# Schematic_2023-08-02.net
KiCad netlist of a schematic drawn in Altium Designer
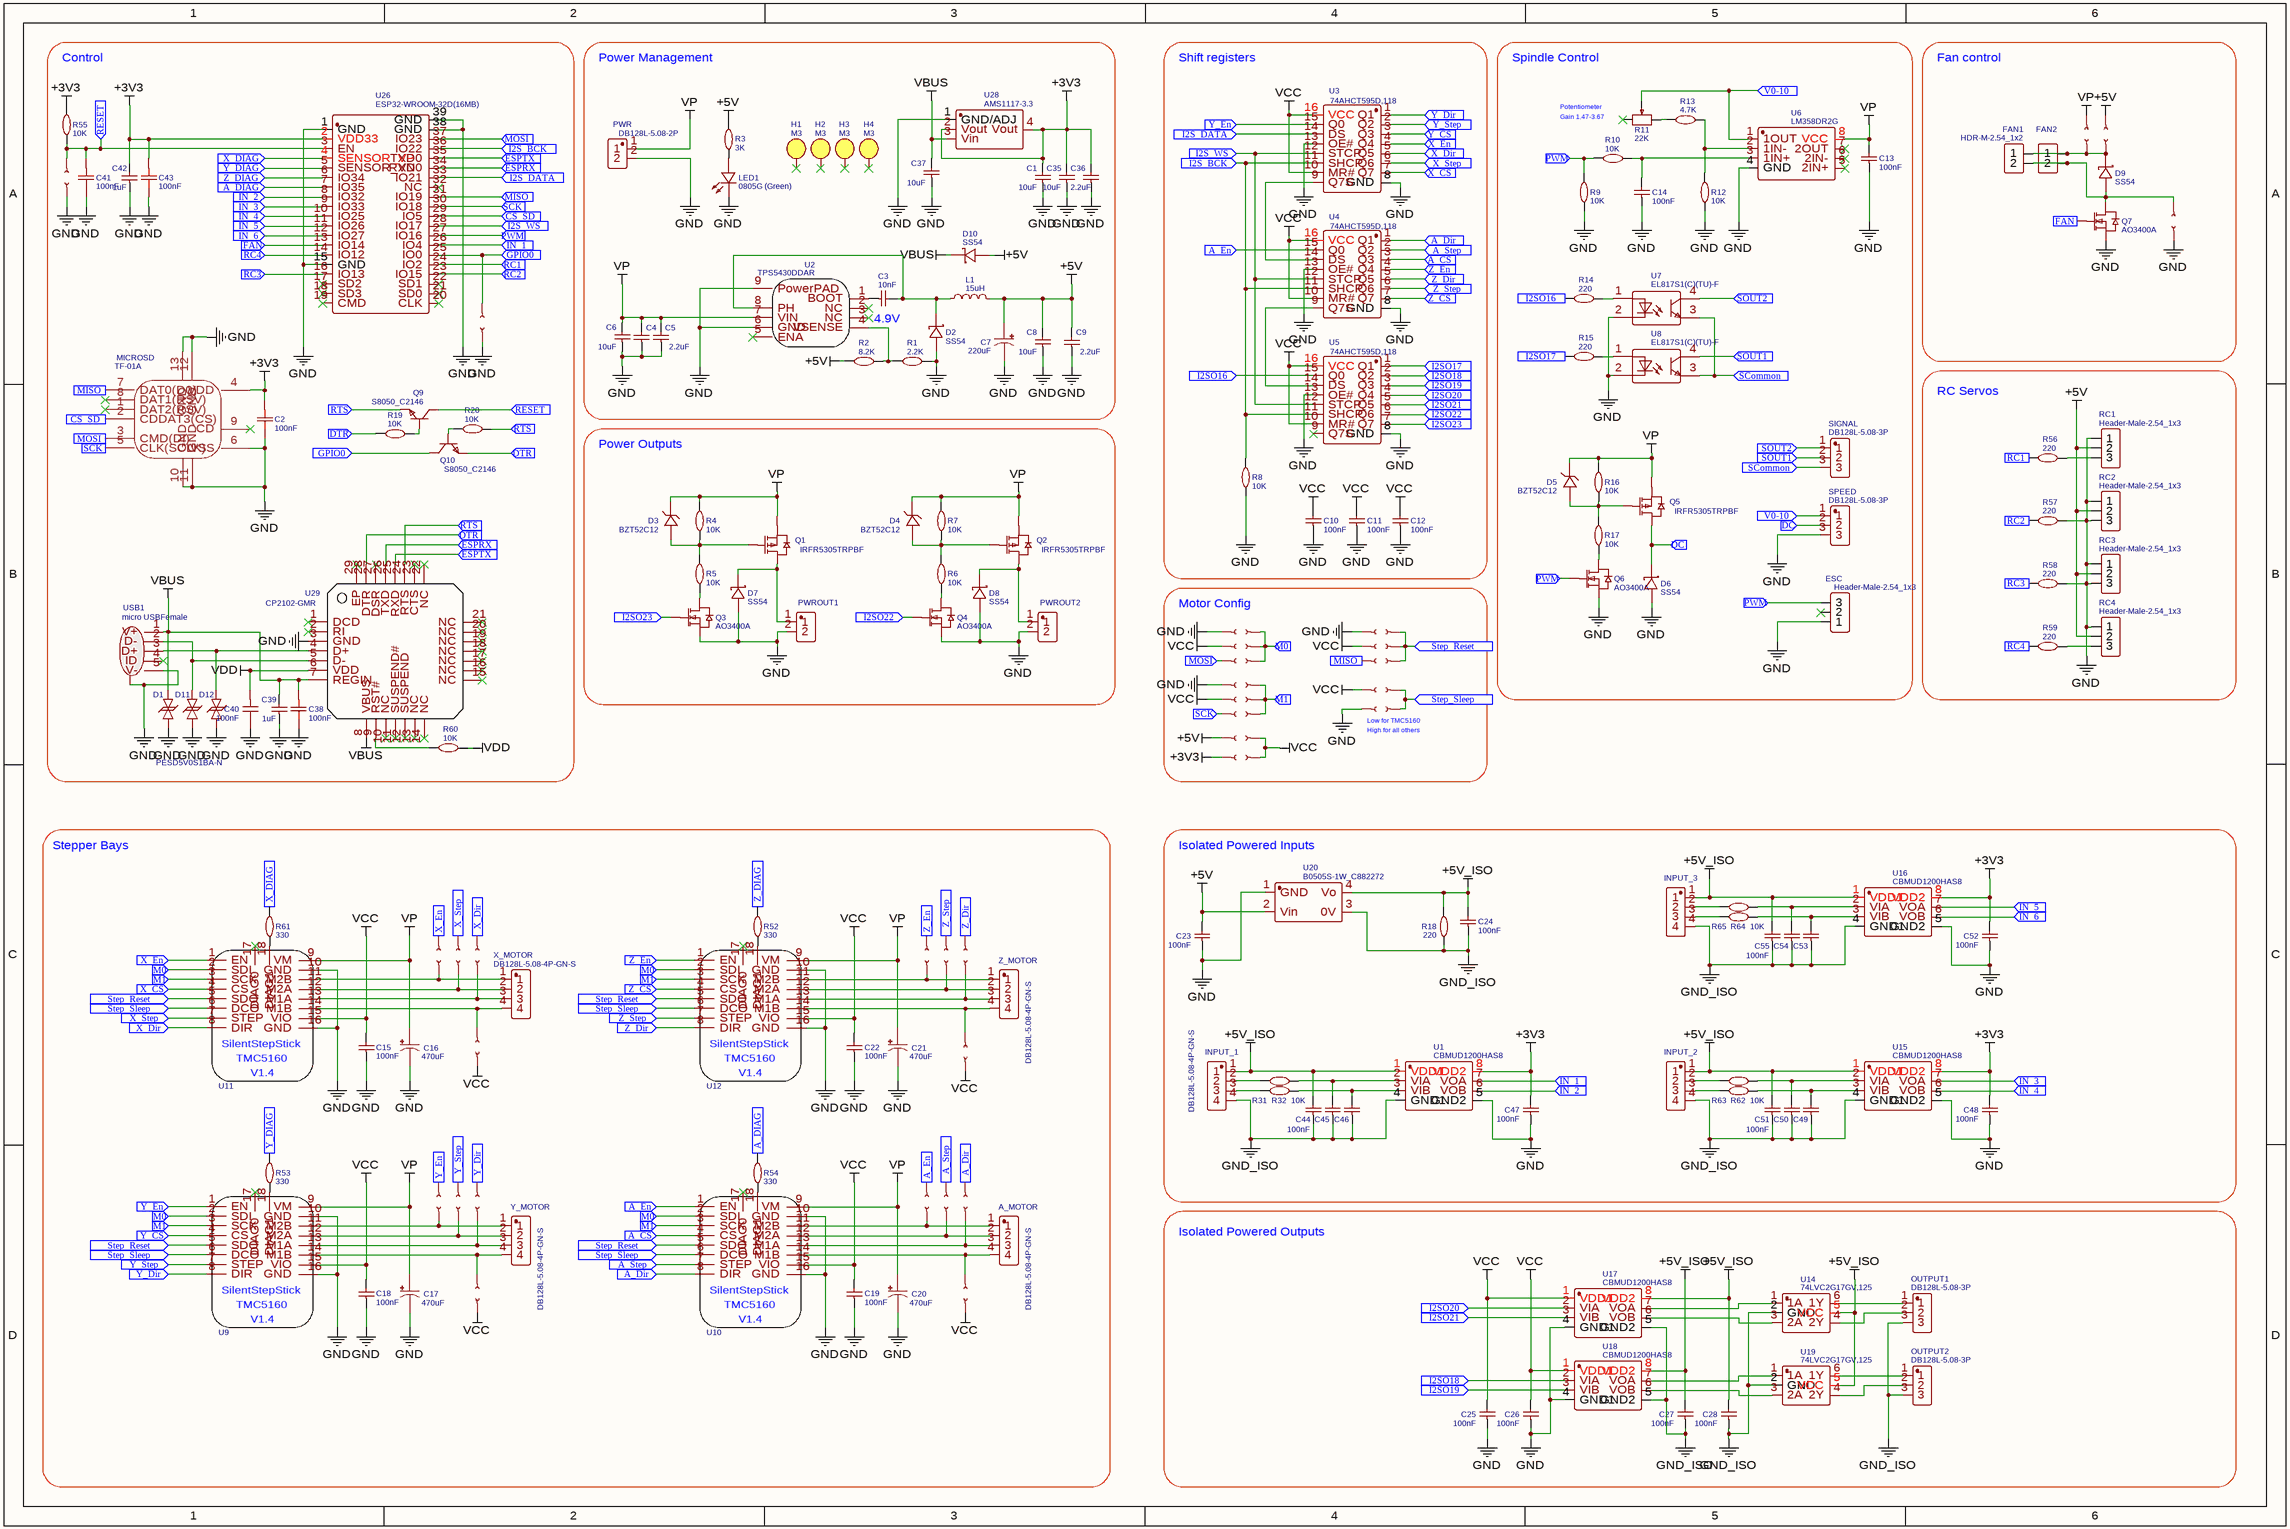
[diagram p0: Schematic_2023-08-02.schdoc]

(export (version "E")
  (design (tool "Eeschema 10.0.6"))
  (components
    (comp (ref "A_MOTOR")
      (value "DB128L-5.08-4P-GN-S")
      (footprint "CONN-TH_4P-5.00_DB128L-5.0-4P-BU-S")
      (fields (field (name "MANUFACTURER") "DIBO") (field (name "CONTRIBUTOR") "LCSC"))
      (libsource (lib "") (part "root_0_DB128L-5.08-4P-GN-S__1"))
    )
    (comp (ref "C1")
      (value "10uF")
      (footprint "C1206")
      (fields (field (name "MANUFACTURER PART") "CL31A106KBHNNNE") (field (name "MANUFACTURER") "SAMSUNG"))
      (libsource (lib "altium-import") (part "root_1_10uF_"))
    )
    (comp (ref "C2")
      (value "100nF")
      (footprint "C0603")
      (fields (field (name "MANUFACTURER") "YAGEO") (field (name "MANUFACTURER PART") "CC0603KRX7R9BB104"))
      (libsource (lib "altium-import") (part "root_1_100nF_"))
    )
    (comp (ref "C3")
      (value "10nF")
      (footprint "C0805")
      (fields (field (name "MANUFACTURER PART") "CL21B103KBANNNC") (field (name "MANUFACTURER") "SAMSUNG"))
      (libsource (lib "altium-import") (part "root_0_10nF_"))
    )
    (comp (ref "C4")
      (value "2.2uF")
      (footprint "C1206")
      (fields (field (name "MANUFACTURER PART") "CL31B225KBHNNNE") (field (name "MANUFACTURER") "SAMSUNG"))
      (libsource (lib "") (part "root_1_2.2uF__1"))
    )
    (comp (ref "C5")
      (value "2.2uF")
      (footprint "C1206")
      (fields (field (name "MANUFACTURER PART") "CL31B225KBHNNNE") (field (name "MANUFACTURER") "SAMSUNG"))
      (libsource (lib "") (part "root_1_2.2uF__1"))
    )
    (comp (ref "C6")
      (value "10uF")
      (footprint "C1206")
      (fields (field (name "MANUFACTURER PART") "CL31A106KBHNNNE") (field (name "MANUFACTURER") "SAMSUNG"))
      (libsource (lib "altium-import") (part "root_1_10uF_"))
    )
    (comp (ref "C7")
      (value "220uF")
      (footprint "CAP-SMD_L7.3-W4.3-R-RD")
      (fields
        (field (name "MANUFACTURER") "TORCH")
        (field (name "MANUFACTURER PART") "CA45-D-10V-220μF-K")
        (field (name "CONTRIBUTOR") "LCSC")
      )
      (libsource (lib "altium-import") (part "root_1_220uF_"))
    )
    (comp (ref "C8")
      (value "10uF")
      (footprint "C1206")
      (fields (field (name "MANUFACTURER PART") "CL31A106KBHNNNE") (field (name "MANUFACTURER") "SAMSUNG"))
      (libsource (lib "altium-import") (part "root_1_10uF_"))
    )
    (comp (ref "C9")
      (value "2.2uF")
      (footprint "C1206")
      (fields (field (name "MANUFACTURER PART") "CL31B225KBHNNNE") (field (name "MANUFACTURER") "SAMSUNG"))
      (libsource (lib "") (part "root_1_2.2uF__1"))
    )
    (comp (ref "C10")
      (value "100nF")
      (footprint "C0805")
      (fields (field (name "MANUFACTURER PART") "CC0805KRX7R9BB104") (field (name "MANUFACTURER") "YAGEO"))
      (libsource (lib "") (part "root_1_100nF__1"))
    )
    (comp (ref "C11")
      (value "100nF")
      (footprint "C0805")
      (fields (field (name "MANUFACTURER PART") "CC0805KRX7R9BB104") (field (name "MANUFACTURER") "YAGEO"))
      (libsource (lib "") (part "root_1_100nF__1"))
    )
    (comp (ref "C12")
      (value "100nF")
      (footprint "C0805")
      (fields (field (name "MANUFACTURER PART") "CC0805KRX7R9BB104") (field (name "MANUFACTURER") "YAGEO"))
      (libsource (lib "") (part "root_1_100nF__1"))
    )
    (comp (ref "C13")
      (value "100nF")
      (footprint "C0805")
      (fields (field (name "MANUFACTURER PART") "CC0805KRX7R9BB104") (field (name "MANUFACTURER") "YAGEO"))
      (libsource (lib "") (part "root_1_100nF__1"))
    )
    (comp (ref "C14")
      (value "100nF")
      (footprint "C0805")
      (fields (field (name "MANUFACTURER PART") "CC0805KRX7R9BB104") (field (name "MANUFACTURER") "YAGEO"))
      (libsource (lib "") (part "root_1_100nF__1"))
    )
    (comp (ref "C15")
      (value "100nF")
      (footprint "C0805")
      (fields (field (name "MANUFACTURER PART") "CC0805KRX7R9BB104") (field (name "MANUFACTURER") "YAGEO"))
      (libsource (lib "") (part "root_1_100nF__1"))
    )
    (comp (ref "C16")
      (value "470uF")
      (footprint "CAP-SMD_BD12.5-L13.0-W13.0-FD")
      (fields
        (field (name "MANUFACTURER") "Changzhou Huawei Elec")
        (field (name "MANUFACTURER PART") "VT1H471MI135000CE0")
        (field (name "CONTRIBUTOR") "LCSC")
      )
      (libsource (lib "altium-import") (part "root_0_470uF_"))
    )
    (comp (ref "C17")
      (value "470uF")
      (footprint "CAP-SMD_BD12.5-L13.0-W13.0-FD")
      (fields
        (field (name "MANUFACTURER") "Changzhou Huawei Elec")
        (field (name "MANUFACTURER PART") "VT1H471MI135000CE0")
        (field (name "CONTRIBUTOR") "LCSC")
      )
      (libsource (lib "altium-import") (part "root_0_470uF_"))
    )
    (comp (ref "C18")
      (value "100nF")
      (footprint "C0805")
      (fields (field (name "MANUFACTURER PART") "CC0805KRX7R9BB104") (field (name "MANUFACTURER") "YAGEO"))
      (libsource (lib "") (part "root_1_100nF__1"))
    )
    (comp (ref "C19")
      (value "100nF")
      (footprint "C0805")
      (fields (field (name "MANUFACTURER PART") "CC0805KRX7R9BB104") (field (name "MANUFACTURER") "YAGEO"))
      (libsource (lib "") (part "root_1_100nF__1"))
    )
    (comp (ref "C20")
      (value "470uF")
      (footprint "CAP-SMD_BD12.5-L13.0-W13.0-FD")
      (fields
        (field (name "MANUFACTURER") "Changzhou Huawei Elec")
        (field (name "MANUFACTURER PART") "VT1H471MI135000CE0")
        (field (name "CONTRIBUTOR") "LCSC")
      )
      (libsource (lib "altium-import") (part "root_0_470uF_"))
    )
    (comp (ref "C21")
      (value "470uF")
      (footprint "CAP-SMD_BD12.5-L13.0-W13.0-FD")
      (fields
        (field (name "MANUFACTURER") "Changzhou Huawei Elec")
        (field (name "MANUFACTURER PART") "VT1H471MI135000CE0")
        (field (name "CONTRIBUTOR") "LCSC")
      )
      (libsource (lib "altium-import") (part "root_0_470uF_"))
    )
    (comp (ref "C22")
      (value "100nF")
      (footprint "C0805")
      (fields (field (name "MANUFACTURER PART") "CC0805KRX7R9BB104") (field (name "MANUFACTURER") "YAGEO"))
      (libsource (lib "") (part "root_1_100nF__1"))
    )
    (comp (ref "C23")
      (value "100nF")
      (footprint "C0805")
      (fields (field (name "MANUFACTURER PART") "CC0805KRX7R9BB104") (field (name "MANUFACTURER") "YAGEO"))
      (libsource (lib "") (part "root_1_100nF__2"))
    )
    (comp (ref "C24")
      (value "100nF")
      (footprint "C0805")
      (fields (field (name "MANUFACTURER PART") "CC0805KRX7R9BB104") (field (name "MANUFACTURER") "YAGEO"))
      (libsource (lib "") (part "root_1_100nF__1"))
    )
    (comp (ref "C25")
      (value "100nF")
      (footprint "C0805")
      (fields (field (name "MANUFACTURER PART") "CC0805KRX7R9BB104") (field (name "MANUFACTURER") "YAGEO"))
      (libsource (lib "") (part "root_1_100nF__2"))
    )
    (comp (ref "C26")
      (value "100nF")
      (footprint "C0805")
      (fields (field (name "MANUFACTURER PART") "CC0805KRX7R9BB104") (field (name "MANUFACTURER") "YAGEO"))
      (libsource (lib "") (part "root_1_100nF__2"))
    )
    (comp (ref "C27")
      (value "100nF")
      (footprint "C0805")
      (fields (field (name "MANUFACTURER PART") "CC0805KRX7R9BB104") (field (name "MANUFACTURER") "YAGEO"))
      (libsource (lib "") (part "root_1_100nF__2"))
    )
    (comp (ref "C28")
      (value "100nF")
      (footprint "C0805")
      (fields (field (name "MANUFACTURER PART") "CC0805KRX7R9BB104") (field (name "MANUFACTURER") "YAGEO"))
      (libsource (lib "") (part "root_1_100nF__2"))
    )
    (comp (ref "C35")
      (value "10uF")
      (footprint "C1206")
      (fields (field (name "MANUFACTURER PART") "CL31A106KBHNNNE") (field (name "MANUFACTURER") "SAMSUNG"))
      (libsource (lib "altium-import") (part "root_1_10uF_"))
    )
    (comp (ref "C36")
      (value "2.2uF")
      (footprint "C1206")
      (fields (field (name "MANUFACTURER PART") "CL31B225KBHNNNE") (field (name "MANUFACTURER") "SAMSUNG"))
      (libsource (lib "altium-import") (part "root_1_2.2uF_"))
    )
    (comp (ref "C37")
      (value "10uF")
      (footprint "C1206")
      (fields (field (name "MANUFACTURER PART") "CL31A106KBHNNNE") (field (name "MANUFACTURER") "SAMSUNG"))
      (libsource (lib "altium-import") (part "root_1_10uF_"))
    )
    (comp (ref "C38")
      (value "100nF")
      (footprint "C0603")
      (fields (field (name "MANUFACTURER") "YAGEO") (field (name "MANUFACTURER PART") "CC0603KRX7R9BB104"))
      (libsource (lib "altium-import") (part "root_1_100nF_"))
    )
    (comp (ref "C39")
      (value "1uF")
      (footprint "C0603")
      (fields (field (name "MANUFACTURER PART") "CL10A105KB8NNNC") (field (name "MANUFACTURER") "SAMSUNG"))
      (libsource (lib "altium-import") (part "root_1_1uF_"))
    )
    (comp (ref "C40")
      (value "100nF")
      (footprint "C0603")
      (fields (field (name "MANUFACTURER") "YAGEO") (field (name "MANUFACTURER PART") "CC0603KRX7R9BB104"))
      (libsource (lib "") (part "root_1_100nF__3"))
    )
    (comp (ref "C41")
      (value "100nF")
      (footprint "C0603")
      (fields (field (name "MANUFACTURER") "YAGEO") (field (name "MANUFACTURER PART") "CC0603KRX7R9BB104"))
      (libsource (lib "altium-import") (part "root_1_100nF_"))
    )
    (comp (ref "C42")
      (value "1uF")
      (footprint "C0603")
      (fields (field (name "MANUFACTURER PART") "CL10A105KB8NNNC") (field (name "MANUFACTURER") "SAMSUNG"))
      (libsource (lib "altium-import") (part "root_1_1uF_"))
    )
    (comp (ref "C43")
      (value "100nF")
      (footprint "C0603")
      (fields (field (name "MANUFACTURER") "YAGEO") (field (name "MANUFACTURER PART") "CC0603KRX7R9BB104"))
      (libsource (lib "altium-import") (part "root_1_100nF_"))
    )
    (comp (ref "C44")
      (value "100nF")
      (footprint "C0805")
      (fields (field (name "MANUFACTURER PART") "CC0805KRX7R9BB104") (field (name "MANUFACTURER") "YAGEO"))
      (libsource (lib "") (part "root_1_100nF__2"))
    )
    (comp (ref "C45")
      (value "100nF")
      (footprint "C0805")
      (fields (field (name "MANUFACTURER PART") "CC0805KRX7R9BB104") (field (name "MANUFACTURER") "YAGEO"))
      (libsource (lib "") (part "root_1_100nF__2"))
    )
    (comp (ref "C46")
      (value "100nF")
      (footprint "C0805")
      (fields (field (name "MANUFACTURER PART") "CC0805KRX7R9BB104") (field (name "MANUFACTURER") "YAGEO"))
      (libsource (lib "") (part "root_1_100nF__2"))
    )
    (comp (ref "C47")
      (value "100nF")
      (footprint "C0805")
      (fields (field (name "MANUFACTURER PART") "CC0805KRX7R9BB104") (field (name "MANUFACTURER") "YAGEO"))
      (libsource (lib "") (part "root_1_100nF__2"))
    )
    (comp (ref "C48")
      (value "100nF")
      (footprint "C0805")
      (fields (field (name "MANUFACTURER PART") "CC0805KRX7R9BB104") (field (name "MANUFACTURER") "YAGEO"))
      (libsource (lib "") (part "root_1_100nF__2"))
    )
    (comp (ref "C49")
      (value "100nF")
      (footprint "C0805")
      (fields (field (name "MANUFACTURER PART") "CC0805KRX7R9BB104") (field (name "MANUFACTURER") "YAGEO"))
      (libsource (lib "") (part "root_1_100nF__2"))
    )
    (comp (ref "C50")
      (value "100nF")
      (footprint "C0805")
      (fields (field (name "MANUFACTURER PART") "CC0805KRX7R9BB104") (field (name "MANUFACTURER") "YAGEO"))
      (libsource (lib "") (part "root_1_100nF__2"))
    )
    (comp (ref "C51")
      (value "100nF")
      (footprint "C0805")
      (fields (field (name "MANUFACTURER PART") "CC0805KRX7R9BB104") (field (name "MANUFACTURER") "YAGEO"))
      (libsource (lib "") (part "root_1_100nF__2"))
    )
    (comp (ref "C52")
      (value "100nF")
      (footprint "C0805")
      (fields (field (name "MANUFACTURER PART") "CC0805KRX7R9BB104") (field (name "MANUFACTURER") "YAGEO"))
      (libsource (lib "") (part "root_1_100nF__2"))
    )
    (comp (ref "C53")
      (value "100nF")
      (footprint "C0805")
      (fields (field (name "MANUFACTURER PART") "CC0805KRX7R9BB104") (field (name "MANUFACTURER") "YAGEO"))
      (libsource (lib "") (part "root_1_100nF__2"))
    )
    (comp (ref "C54")
      (value "100nF")
      (footprint "C0805")
      (fields (field (name "MANUFACTURER PART") "CC0805KRX7R9BB104") (field (name "MANUFACTURER") "YAGEO"))
      (libsource (lib "") (part "root_1_100nF__2"))
    )
    (comp (ref "C55")
      (value "100nF")
      (footprint "C0805")
      (fields (field (name "MANUFACTURER PART") "CC0805KRX7R9BB104") (field (name "MANUFACTURER") "YAGEO"))
      (libsource (lib "") (part "root_1_100nF__2"))
    )
    (comp (ref "D1")
      (value "PESD5V0S1BA-N")
      (footprint "SOD-323_L1.8-W1.3-LS2.5-BI")
      (fields (field (name "MANUFACTURER") "Bourne Semicon (Shenzhen)") (field (name "CONTRIBUTOR") "LCSC"))
      (libsource (lib "altium-import") (part "root_1_PESD5V0S1BA-N_"))
    )
    (comp (ref "D2")
      (value "SS54")
      (footprint "SMA_L4.4-W2.8-LS5.4-R-RD")
      (fields (field (name "MANUFACTURER") "MDD"))
      (libsource (lib "altium-import") (part "root_3_SS54_"))
    )
    (comp (ref "D3")
      (value "BZT52C12")
      (footprint "SOD-123_L2.7-W1.6-LS3.7-RD")
      (fields (field (name "MANUFACTURER") "MDD") (field (name "CONTRIBUTOR") "LCSC"))
      (libsource (lib "altium-import") (part "root_3_BZT52C12_"))
    )
    (comp (ref "D4")
      (value "BZT52C12")
      (footprint "SOD-123_L2.7-W1.6-LS3.7-RD")
      (fields (field (name "MANUFACTURER") "MDD") (field (name "CONTRIBUTOR") "LCSC"))
      (libsource (lib "altium-import") (part "root_3_BZT52C12_"))
    )
    (comp (ref "D5")
      (value "BZT52C12")
      (footprint "SOD-123_L2.7-W1.6-LS3.7-RD")
      (fields (field (name "MANUFACTURER") "MDD") (field (name "CONTRIBUTOR") "LCSC"))
      (libsource (lib "altium-import") (part "root_3_BZT52C12_"))
    )
    (comp (ref "D6")
      (value "SS54")
      (footprint "SMA_L4.4-W2.8-LS5.4-R-RD")
      (fields (field (name "MANUFACTURER") "MDD"))
      (libsource (lib "altium-import") (part "root_3_SS54_"))
    )
    (comp (ref "D7")
      (value "SS54")
      (footprint "SMA_L4.4-W2.8-LS5.4-R-RD")
      (fields (field (name "MANUFACTURER") "MDD"))
      (libsource (lib "altium-import") (part "root_3_SS54_"))
    )
    (comp (ref "D8")
      (value "SS54")
      (footprint "SMA_L4.4-W2.8-LS5.4-R-RD")
      (fields (field (name "MANUFACTURER") "MDD"))
      (libsource (lib "altium-import") (part "root_3_SS54_"))
    )
    (comp (ref "D9")
      (value "SS54")
      (footprint "SMA_L4.4-W2.8-LS5.4-R-RD")
      (fields (field (name "MANUFACTURER") "MDD"))
      (libsource (lib "altium-import") (part "root_3_SS54_"))
    )
    (comp (ref "D10")
      (value "SS54")
      (footprint "SMA_L4.4-W2.8-LS5.4-R-RD")
      (fields (field (name "MANUFACTURER") "MDD"))
      (libsource (lib "altium-import") (part "root_0_SS54_"))
    )
    (comp (ref "D11")
      (value "PESD5V0S1BA-N")
      (footprint "SOD-323_L1.8-W1.3-LS2.5-BI")
      (fields (field (name "MANUFACTURER") "Bourne Semicon (Shenzhen)") (field (name "CONTRIBUTOR") "LCSC"))
      (libsource (lib "altium-import") (part "root_1_PESD5V0S1BA-N_"))
    )
    (comp (ref "D12")
      (value "PESD5V0S1BA-N")
      (footprint "SOD-323_L1.8-W1.3-LS2.5-BI")
      (fields (field (name "MANUFACTURER") "Bourne Semicon (Shenzhen)") (field (name "CONTRIBUTOR") "LCSC"))
      (libsource (lib "altium-import") (part "root_1_PESD5V0S1BA-N_"))
    )
    (comp (ref "ESC")
      (value "Header-Male-2.54_1x3")
      (footprint "HDR-TH_3P-P2.54-V-M-1")
      (fields (field (name "MANUFACTURER") "BOOMELE") (field (name "MANUFACTURER PART") "Header2.54mm 1*3P"))
      (libsource (lib "altium-import") (part "root_2_Header-Male-2.54_1x3_"))
    )
    (comp (ref "FAN1")
      (value "HDR-M-2.54_1x2")
      (footprint "HDR-M-2.54_1X2")
      (fields (field (name "CONTRIBUTOR") "LCEDA_Lib"))
      (libsource (lib "altium-import") (part "root_0_HDR-M-2.54_1x2_"))
    )
    (comp (ref "FAN2")
      (value "HDR-M-2.54_1x2")
      (footprint "HDR-M-2.54_1X2")
      (fields (field (name "CONTRIBUTOR") "LCEDA_Lib"))
      (libsource (lib "altium-import") (part "root_0_HDR-M-2.54_1x2_"))
    )
    (comp (ref "H1")
      (value "M3")
      (footprint "M3 CHASSIS")
      (fields (field (name "CONTRIBUTOR") "maitrai"))
      (libsource (lib "altium-import") (part "root_0_M3_"))
    )
    (comp (ref "H2")
      (value "M3")
      (footprint "M3 CHASSIS")
      (fields (field (name "CONTRIBUTOR") "maitrai"))
      (libsource (lib "altium-import") (part "root_0_M3_"))
    )
    (comp (ref "H3")
      (value "M3")
      (footprint "M3 CHASSIS")
      (fields (field (name "CONTRIBUTOR") "maitrai"))
      (libsource (lib "altium-import") (part "root_0_M3_"))
    )
    (comp (ref "H4")
      (value "M3")
      (footprint "M3 CHASSIS")
      (fields (field (name "CONTRIBUTOR") "maitrai"))
      (libsource (lib "altium-import") (part "root_0_M3_"))
    )
    (comp (ref "INPUT_1")
      (value "DB128L-5.08-4P-GN-S")
      (footprint "CONN-TH_4P-5.00_DB128L-5.0-4P-BU-S")
      (fields (field (name "MANUFACTURER") "DIBO") (field (name "CONTRIBUTOR") "LCSC"))
      (libsource (lib "altium-import") (part "root_0_DB128L-5.08-4P-GN-S_"))
    )
    (comp (ref "INPUT_2")
      (value "DB128L-5.08-4P-GN-S")
      (footprint "CONN-TH_4P-5.00_DB128L-5.0-4P-BU-S")
      (fields (field (name "MANUFACTURER") "DIBO") (field (name "CONTRIBUTOR") "LCSC"))
      (libsource (lib "altium-import") (part "root_0_DB128L-5.08-4P-GN-S_"))
    )
    (comp (ref "INPUT_3")
      (value "DB128L-5.08-4P-GN-S")
      (footprint "CONN-TH_4P-5.00_DB128L-5.0-4P-BU-S")
      (fields (field (name "MANUFACTURER") "DIBO") (field (name "CONTRIBUTOR") "LCSC"))
      (libsource (lib "altium-import") (part "root_0_DB128L-5.08-4P-GN-S_"))
    )
    (comp (ref "JP1")
      (value "JUMPER-PAD-2")
      (footprint "JUMPER_SOLDER_2")
      (fields (field (name "CONTRIBUTOR") "IPR SYSTEMS EDA"))
      (libsource (lib "altium-import") (part "root_1_JUMPER-PAD-2_"))
    )
    (comp (ref "JP2")
      (value "JUMPER-PAD-2")
      (footprint "JUMPER_SOLDER_2")
      (fields (field (name "CONTRIBUTOR") "IPR SYSTEMS EDA"))
      (libsource (lib "altium-import") (part "root_1_JUMPER-PAD-2_"))
    )
    (comp (ref "JP3")
      (value "JUMPER-PAD-2")
      (footprint "JUMPER_SOLDER_2")
      (fields (field (name "CONTRIBUTOR") "IPR SYSTEMS EDA"))
      (libsource (lib "altium-import") (part "root_1_JUMPER-PAD-2_"))
    )
    (comp (ref "JP4")
      (value "JUMPER-PAD-2")
      (footprint "JUMPER_SOLDER_2")
      (fields (field (name "CONTRIBUTOR") "IPR SYSTEMS EDA"))
      (libsource (lib "altium-import") (part "root_1_JUMPER-PAD-2_"))
    )
    (comp (ref "JP5")
      (value "JUMPER-PAD-2")
      (footprint "JUMPER_SOLDER_2")
      (fields (field (name "CONTRIBUTOR") "IPR SYSTEMS EDA"))
      (libsource (lib "altium-import") (part "root_0_JUMPER-PAD-2_"))
    )
    (comp (ref "JP6")
      (value "JUMPER-PAD-2")
      (footprint "JUMPER_SOLDER_2")
      (fields (field (name "CONTRIBUTOR") "IPR SYSTEMS EDA"))
      (libsource (lib "altium-import") (part "root_0_JUMPER-PAD-2_"))
    )
    (comp (ref "JP7")
      (value "JUMPER-PAD-2")
      (footprint "JUMPER_SOLDER_2")
      (fields (field (name "CONTRIBUTOR") "IPR SYSTEMS EDA"))
      (libsource (lib "altium-import") (part "root_0_JUMPER-PAD-2_"))
    )
    (comp (ref "JP8")
      (value "JUMPER-PAD-2")
      (footprint "JUMPER_SOLDER_2")
      (fields (field (name "CONTRIBUTOR") "IPR SYSTEMS EDA"))
      (libsource (lib "altium-import") (part "root_0_JUMPER-PAD-2_"))
    )
    (comp (ref "JP9")
      (value "JUMPER-PAD-2")
      (footprint "JUMPER_SOLDER_2")
      (fields (field (name "CONTRIBUTOR") "IPR SYSTEMS EDA"))
      (libsource (lib "altium-import") (part "root_0_JUMPER-PAD-2_"))
    )
    (comp (ref "JP10")
      (value "JUMPER-PAD-2")
      (footprint "JUMPER_SOLDER_2")
      (fields (field (name "CONTRIBUTOR") "IPR SYSTEMS EDA"))
      (libsource (lib "altium-import") (part "root_0_JUMPER-PAD-2_"))
    )
    (comp (ref "JP11")
      (value "JUMPER-PAD-2")
      (footprint "JUMPER_SOLDER_2")
      (fields (field (name "CONTRIBUTOR") "IPR SYSTEMS EDA"))
      (libsource (lib "altium-import") (part "root_0_JUMPER-PAD-2_"))
    )
    (comp (ref "JP12")
      (value "JUMPER-PAD-2")
      (footprint "JUMPER_SOLDER_2")
      (fields (field (name "CONTRIBUTOR") "IPR SYSTEMS EDA"))
      (libsource (lib "altium-import") (part "root_0_JUMPER-PAD-2_"))
    )
    (comp (ref "JP13")
      (value "JUMPER-PAD-2")
      (footprint "JUMPER_SOLDER_2")
      (fields (field (name "CONTRIBUTOR") "IPR SYSTEMS EDA"))
      (libsource (lib "altium-import") (part "root_0_JUMPER-PAD-2_"))
    )
    (comp (ref "JP14")
      (value "JUMPER-PAD-2")
      (footprint "JUMPER_SOLDER_2")
      (fields (field (name "CONTRIBUTOR") "IPR SYSTEMS EDA"))
      (libsource (lib "altium-import") (part "root_0_JUMPER-PAD-2_"))
    )
    (comp (ref "JP15")
      (value "JUMPER-PAD-2")
      (footprint "JUMPER_SOLDER_2")
      (fields (field (name "CONTRIBUTOR") "IPR SYSTEMS EDA"))
      (libsource (lib "altium-import") (part "root_1_JUMPER-PAD-2_"))
    )
    (comp (ref "JP16")
      (value "JUMPER-PAD-2")
      (footprint "JUMPER_SOLDER_2")
      (fields (field (name "CONTRIBUTOR") "IPR SYSTEMS EDA"))
      (libsource (lib "altium-import") (part "root_1_JUMPER-PAD-2_"))
    )
    (comp (ref "JP17")
      (value "JUMPER-PAD-2")
      (footprint "JUMPER_SOLDER_2")
      (fields (field (name "CONTRIBUTOR") "IPR SYSTEMS EDA"))
      (libsource (lib "altium-import") (part "root_1_JUMPER-PAD-2_"))
    )
    (comp (ref "JP18")
      (value "JUMPER-PAD-2")
      (footprint "JUMPER_SOLDER_2")
      (fields (field (name "CONTRIBUTOR") "IPR SYSTEMS EDA"))
      (libsource (lib "altium-import") (part "root_1_JUMPER-PAD-2_"))
    )
    (comp (ref "JP19")
      (value "JUMPER-PAD-2")
      (footprint "JUMPER_SOLDER_2")
      (fields (field (name "CONTRIBUTOR") "IPR SYSTEMS EDA"))
      (libsource (lib "altium-import") (part "root_1_JUMPER-PAD-2_"))
    )
    (comp (ref "JP20")
      (value "JUMPER-PAD-2")
      (footprint "JUMPER_SOLDER_2")
      (fields (field (name "CONTRIBUTOR") "IPR SYSTEMS EDA"))
      (libsource (lib "altium-import") (part "root_1_JUMPER-PAD-2_"))
    )
    (comp (ref "JP21")
      (value "JUMPER-PAD-2")
      (footprint "JUMPER_SOLDER_2")
      (fields (field (name "CONTRIBUTOR") "IPR SYSTEMS EDA"))
      (libsource (lib "altium-import") (part "root_1_JUMPER-PAD-2_"))
    )
    (comp (ref "JP22")
      (value "JUMPER-PAD-2")
      (footprint "JUMPER_SOLDER_2")
      (fields (field (name "CONTRIBUTOR") "IPR SYSTEMS EDA"))
      (libsource (lib "altium-import") (part "root_1_JUMPER-PAD-2_"))
    )
    (comp (ref "JP23")
      (value "JUMPER-PAD-2")
      (footprint "JUMPER_SOLDER_2")
      (fields (field (name "CONTRIBUTOR") "IPR SYSTEMS EDA"))
      (libsource (lib "altium-import") (part "root_1_JUMPER-PAD-2_"))
    )
    (comp (ref "JP24")
      (value "JUMPER-PAD-2")
      (footprint "JUMPER_SOLDER_2")
      (fields (field (name "CONTRIBUTOR") "IPR SYSTEMS EDA"))
      (libsource (lib "altium-import") (part "root_1_JUMPER-PAD-2_"))
    )
    (comp (ref "JP25")
      (value "JUMPER-PAD-2")
      (footprint "JUMPER_SOLDER_2")
      (fields (field (name "CONTRIBUTOR") "IPR SYSTEMS EDA"))
      (libsource (lib "altium-import") (part "root_1_JUMPER-PAD-2_"))
    )
    (comp (ref "JP26")
      (value "JUMPER-PAD-2")
      (footprint "JUMPER_SOLDER_2")
      (fields (field (name "CONTRIBUTOR") "IPR SYSTEMS EDA"))
      (libsource (lib "altium-import") (part "root_1_JUMPER-PAD-2_"))
    )
    (comp (ref "JP27")
      (value "JUMPER-PAD-2")
      (footprint "JUMPER_SOLDER_2")
      (fields (field (name "CONTRIBUTOR") "IPR SYSTEMS EDA"))
      (libsource (lib "altium-import") (part "root_1_JUMPER-PAD-2_"))
    )
    (comp (ref "JP28")
      (value "JUMPER-PAD-2")
      (footprint "JUMPER_SOLDER_2")
      (fields (field (name "CONTRIBUTOR") "IPR SYSTEMS EDA"))
      (libsource (lib "altium-import") (part "root_1_JUMPER-PAD-2_"))
    )
    (comp (ref "JP29")
      (value "JUMPER-PAD-2")
      (footprint "JUMPER_SOLDER_2")
      (fields (field (name "CONTRIBUTOR") "IPR SYSTEMS EDA"))
      (libsource (lib "altium-import") (part "root_1_JUMPER-PAD-2_"))
    )
    (comp (ref "JP30")
      (value "JUMPER-PAD-2")
      (footprint "JUMPER_SOLDER_2")
      (fields (field (name "CONTRIBUTOR") "IPR SYSTEMS EDA"))
      (libsource (lib "altium-import") (part "root_0_JUMPER-PAD-2_"))
    )
    (comp (ref "JP31")
      (value "JUMPER-PAD-2")
      (footprint "JUMPER_SOLDER_2")
      (fields (field (name "CONTRIBUTOR") "IPR SYSTEMS EDA"))
      (libsource (lib "altium-import") (part "root_0_JUMPER-PAD-2_"))
    )
    (comp (ref "JP32")
      (value "JUMPER-PAD-2")
      (footprint "JUMPER_SOLDER_2")
      (fields (field (name "CONTRIBUTOR") "IPR SYSTEMS EDA"))
      (libsource (lib "altium-import") (part "root_0_JUMPER-PAD-2_"))
    )
    (comp (ref "JP33")
      (value "JUMPER-PAD-2")
      (footprint "JUMPER_SOLDER_2")
      (fields (field (name "CONTRIBUTOR") "IPR SYSTEMS EDA"))
      (libsource (lib "altium-import") (part "root_1_JUMPER-PAD-2_"))
    )
    (comp (ref "JP34")
      (value "JUMPER-PAD-2")
      (footprint "JUMPER_SOLDER_2")
      (fields (field (name "CONTRIBUTOR") "IPR SYSTEMS EDA"))
      (libsource (lib "altium-import") (part "root_1_JUMPER-PAD-2_"))
    )
    (comp (ref "L1")
      (value "15uH")
      (footprint "IND-SMD_L7.3-W6.6")
      (fields (field (name "MANUFACTURER") "SXN") (field (name "MANUFACTURER PART") "SMMS0630-150M"))
      (libsource (lib "altium-import") (part "root_0_15uH_"))
    )
    (comp (ref "LED1")
      (value "0805G (Green)")
      (footprint "LED0805-RD_GREEN")
      (fields (field (name "MANUFACTURER") "KENTO"))
      (libsource (lib "altium-import") (part "root_1_0805G (Green)_"))
    )
    (comp (ref "MICROSD")
      (value "TF-01A")
      (footprint "TF-SMD_TF-01A")
      (fields (field (name "MANUFACTURER") "HRO"))
      (libsource (lib "altium-import") (part "root_0_TF-01A_"))
    )
    (comp (ref "OUTPUT1")
      (value "DB128L-5.08-3P")
      (footprint "CONN-TH_DB128L-5.08-3P")
      (fields (field (name "MANUFACTURER") "DIBO") (field (name "CONTRIBUTOR") "LCSC"))
      (libsource (lib "altium-import") (part "root_0_DB128L-5.08-3P_"))
    )
    (comp (ref "OUTPUT2")
      (value "DB128L-5.08-3P")
      (footprint "CONN-TH_DB128L-5.08-3P")
      (fields (field (name "MANUFACTURER") "DIBO") (field (name "CONTRIBUTOR") "LCSC"))
      (libsource (lib "altium-import") (part "root_0_DB128L-5.08-3P_"))
    )
    (comp (ref "PWR")
      (value "DB128L-5.08-2P")
      (footprint "CONN-TH_2P-P5.08_DB128L-5.08-2P")
      (fields (field (name "MANUFACTURER") "DIBO") (field (name "CONTRIBUTOR") "LCSC"))
      (libsource (lib "") (part "root_0_DB128L-5.08-2P__1"))
    )
    (comp (ref "PWROUT1")
      (value "DB128L-5.08-2P")
      (footprint "CONN-TH_2P-P5.08_DB128L-5.08-2P")
      (fields (field (name "MANUFACTURER") "DIBO") (field (name "CONTRIBUTOR") "LCSC"))
      (libsource (lib "altium-import") (part "root_0_DB128L-5.08-2P_"))
    )
    (comp (ref "PWROUT2")
      (value "DB128L-5.08-2P")
      (footprint "CONN-TH_2P-P5.08_DB128L-5.08-2P")
      (fields (field (name "MANUFACTURER") "DIBO") (field (name "CONTRIBUTOR") "LCSC"))
      (libsource (lib "altium-import") (part "root_0_DB128L-5.08-2P_"))
    )
    (comp (ref "Q1")
      (value "IRFR5305TRPBF")
      (footprint "TO-252-3_L6.5-W5.8-P4.58-TR")
      (fields (field (name "MANUFACTURER") "IR"))
      (libsource (lib "altium-import") (part "root_2_IRFR5305TRPBF_"))
    )
    (comp (ref "Q2")
      (value "IRFR5305TRPBF")
      (footprint "TO-252-3_L6.5-W5.8-P4.58-TR")
      (fields (field (name "MANUFACTURER") "IR"))
      (libsource (lib "altium-import") (part "root_2_IRFR5305TRPBF_"))
    )
    (comp (ref "Q3")
      (value "AO3400A")
      (footprint "SOT-23-3_L2.9-W1.6-P1.90-LS2.8-BR")
      (fields (field (name "MANUFACTURER") "AOS"))
      (libsource (lib "altium-import") (part "root_0_AO3400A_"))
    )
    (comp (ref "Q4")
      (value "AO3400A")
      (footprint "SOT-23-3_L2.9-W1.6-P1.90-LS2.8-BR")
      (fields (field (name "MANUFACTURER") "AOS"))
      (libsource (lib "altium-import") (part "root_0_AO3400A_"))
    )
    (comp (ref "Q5")
      (value "IRFR5305TRPBF")
      (footprint "TO-252-3_L6.5-W5.8-P4.58-TR")
      (fields (field (name "MANUFACTURER") "IR"))
      (libsource (lib "altium-import") (part "root_2_IRFR5305TRPBF_"))
    )
    (comp (ref "Q6")
      (value "AO3400A")
      (footprint "SOT-23-3_L2.9-W1.6-P1.90-LS2.8-BR")
      (fields (field (name "MANUFACTURER") "AOS"))
      (libsource (lib "altium-import") (part "root_0_AO3400A_"))
    )
    (comp (ref "Q7")
      (value "AO3400A")
      (footprint "SOT-23-3_L2.9-W1.6-P1.90-LS2.8-BR")
      (fields (field (name "MANUFACTURER") "AOS"))
      (libsource (lib "altium-import") (part "root_0_AO3400A_"))
    )
    (comp (ref "Q9")
      (value "S8050_C2146")
      (footprint "SOT-23-3_L3.0-W1.7-P0.95-LS2.9-BR")
      (fields (field (name "MANUFACTURER") "CJ") (field (name "MANUFACTURER PART") "S8050"))
      (libsource (lib "altium-import") (part "root_1_S8050_C2146_"))
    )
    (comp (ref "Q10")
      (value "S8050_C2146")
      (footprint "SOT-23-3_L3.0-W1.7-P0.95-LS2.9-BR")
      (fields (field (name "MANUFACTURER") "CJ") (field (name "MANUFACTURER PART") "S8050"))
      (libsource (lib "altium-import") (part "root_3_S8050_C2146_"))
    )
    (comp (ref "R1")
      (value "2.2K")
      (footprint "R0805")
      (fields (field (name "MANUFACTURER") "UniOhm") (field (name "MANUFACTURER PART") "0805W8F2201T5E"))
      (libsource (lib "altium-import") (part "root_0_2.2K_"))
    )
    (comp (ref "R2")
      (value "8.2K")
      (footprint "R0805")
      (fields (field (name "MANUFACTURER") "UniOhm") (field (name "MANUFACTURER PART") "0805W8F8201T5E"))
      (libsource (lib "altium-import") (part "root_0_8.2K_"))
    )
    (comp (ref "R3")
      (value "3K")
      (footprint "R0805")
      (fields (field (name "MANUFACTURER") "UniOhm") (field (name "MANUFACTURER PART") "0805W8F3001T5E"))
      (libsource (lib "altium-import") (part "root_1_3K_"))
    )
    (comp (ref "R4")
      (value "10K")
      (footprint "R0805")
      (fields (field (name "MANUFACTURER") "UniOhm") (field (name "MANUFACTURER PART") "0805W8F1002T5E"))
      (libsource (lib "altium-import") (part "root_3_10K_"))
    )
    (comp (ref "R5")
      (value "10K")
      (footprint "R0805")
      (fields (field (name "MANUFACTURER") "UniOhm") (field (name "MANUFACTURER PART") "0805W8F1002T5E"))
      (libsource (lib "altium-import") (part "root_3_10K_"))
    )
    (comp (ref "R6")
      (value "10K")
      (footprint "R0805")
      (fields (field (name "MANUFACTURER") "UniOhm") (field (name "MANUFACTURER PART") "0805W8F1002T5E"))
      (libsource (lib "altium-import") (part "root_3_10K_"))
    )
    (comp (ref "R7")
      (value "10K")
      (footprint "R0805")
      (fields (field (name "MANUFACTURER") "UniOhm") (field (name "MANUFACTURER PART") "0805W8F1002T5E"))
      (libsource (lib "altium-import") (part "root_3_10K_"))
    )
    (comp (ref "R8")
      (value "10K")
      (footprint "R0805")
      (fields (field (name "MANUFACTURER") "UniOhm") (field (name "MANUFACTURER PART") "0805W8F1002T5E"))
      (libsource (lib "altium-import") (part "root_3_10K_"))
    )
    (comp (ref "R9")
      (value "10K")
      (footprint "R0805")
      (fields (field (name "MANUFACTURER") "UniOhm") (field (name "MANUFACTURER PART") "0805W8F1002T5E"))
      (libsource (lib "altium-import") (part "root_3_10K_"))
    )
    (comp (ref "R10")
      (value "10K")
      (footprint "R0805")
      (fields (field (name "MANUFACTURER") "UniOhm") (field (name "MANUFACTURER PART") "0805W8F1002T5E"))
      (libsource (lib "altium-import") (part "root_0_10K_"))
    )
    (comp (ref "R11")
      (value "22K")
      (footprint "RES-ADJ-SMD_VG039NCH")
      (fields
        (field (name "MANUFACTURER") "HDK")
        (field (name "MANUFACTURER PART") "VG039NCHXTB223")
        (field (name "CONTRIBUTOR") "LCSC")
      )
      (libsource (lib "altium-import") (part "root_3_22K_"))
    )
    (comp (ref "R12")
      (value "10K")
      (footprint "R0805")
      (fields (field (name "MANUFACTURER") "UniOhm") (field (name "MANUFACTURER PART") "0805W8F1002T5E"))
      (libsource (lib "altium-import") (part "root_1_10K_"))
    )
    (comp (ref "R13")
      (value "4.7K")
      (footprint "R0805")
      (fields (field (name "MANUFACTURER") "UniOhm") (field (name "MANUFACTURER PART") "0805W8F4701T5E"))
      (libsource (lib "altium-import") (part "root_2_4.7K_"))
    )
    (comp (ref "R14")
      (value "220")
      (footprint "R0805")
      (fields (field (name "MANUFACTURER") "UniOhm") (field (name "MANUFACTURER PART") "0805W8F2200T5E"))
      (libsource (lib "altium-import") (part "root_0_220_"))
    )
    (comp (ref "R15")
      (value "220")
      (footprint "R0805")
      (fields (field (name "MANUFACTURER") "UniOhm") (field (name "MANUFACTURER PART") "0805W8F2200T5E"))
      (libsource (lib "altium-import") (part "root_0_220_"))
    )
    (comp (ref "R16")
      (value "10K")
      (footprint "R0805")
      (fields (field (name "MANUFACTURER") "UniOhm") (field (name "MANUFACTURER PART") "0805W8F1002T5E"))
      (libsource (lib "altium-import") (part "root_3_10K_"))
    )
    (comp (ref "R17")
      (value "10K")
      (footprint "R0805")
      (fields (field (name "MANUFACTURER") "UniOhm") (field (name "MANUFACTURER PART") "0805W8F1002T5E"))
      (libsource (lib "altium-import") (part "root_3_10K_"))
    )
    (comp (ref "R18")
      (value "220")
      (footprint "R0805")
      (fields (field (name "MANUFACTURER") "UniOhm") (field (name "MANUFACTURER PART") "0805W8F2200T5E"))
      (libsource (lib "altium-import") (part "root_1_220_"))
    )
    (comp (ref "R19")
      (value "10K")
      (footprint "R0603")
      (fields (field (name "MANUFACTURER") "UniOhm") (field (name "MANUFACTURER PART") "0603WAF1002T5E"))
      (libsource (lib "altium-import") (part "root_2_10K_"))
    )
    (comp (ref "R20")
      (value "10K")
      (footprint "R0603")
      (fields (field (name "MANUFACTURER") "UniOhm") (field (name "MANUFACTURER PART") "0603WAF1002T5E"))
      (libsource (lib "altium-import") (part "root_2_10K_"))
    )
    (comp (ref "R31")
      (value "10K")
      (footprint "R0805")
      (fields (field (name "MANUFACTURER") "UniOhm") (field (name "MANUFACTURER PART") "0805W8F1002T5E"))
      (libsource (lib "altium-import") (part "root_2_10K_"))
    )
    (comp (ref "R32")
      (value "10K")
      (footprint "R0805")
      (fields (field (name "MANUFACTURER") "UniOhm") (field (name "MANUFACTURER PART") "0805W8F1002T5E"))
      (libsource (lib "altium-import") (part "root_2_10K_"))
    )
    (comp (ref "R52")
      (value "330")
      (footprint "R0805")
      (fields (field (name "MANUFACTURER") "UniOhm") (field (name "MANUFACTURER PART") "0805W8F3300T5E"))
      (libsource (lib "altium-import") (part "root_1_330_"))
    )
    (comp (ref "R53")
      (value "330")
      (footprint "R0805")
      (fields (field (name "MANUFACTURER") "UniOhm") (field (name "MANUFACTURER PART") "0805W8F3300T5E"))
      (libsource (lib "altium-import") (part "root_1_330_"))
    )
    (comp (ref "R54")
      (value "330")
      (footprint "R0805")
      (fields (field (name "MANUFACTURER") "UniOhm") (field (name "MANUFACTURER PART") "0805W8F3300T5E"))
      (libsource (lib "altium-import") (part "root_1_330_"))
    )
    (comp (ref "R55")
      (value "10K")
      (footprint "R0603")
      (fields (field (name "MANUFACTURER") "UniOhm") (field (name "MANUFACTURER PART") "0603WAF1002T5E"))
      (libsource (lib "altium-import") (part "root_1_10K_"))
    )
    (comp (ref "R56")
      (value "220")
      (footprint "R0805")
      (fields (field (name "MANUFACTURER") "UniOhm") (field (name "MANUFACTURER PART") "0805W8F2200T5E"))
      (libsource (lib "altium-import") (part "root_0_220_"))
    )
    (comp (ref "R57")
      (value "220")
      (footprint "R0805")
      (fields (field (name "MANUFACTURER") "UniOhm") (field (name "MANUFACTURER PART") "0805W8F2200T5E"))
      (libsource (lib "altium-import") (part "root_0_220_"))
    )
    (comp (ref "R58")
      (value "220")
      (footprint "R0805")
      (fields (field (name "MANUFACTURER") "UniOhm") (field (name "MANUFACTURER PART") "0805W8F2200T5E"))
      (libsource (lib "altium-import") (part "root_0_220_"))
    )
    (comp (ref "R59")
      (value "220")
      (footprint "R0805")
      (fields (field (name "MANUFACTURER") "UniOhm") (field (name "MANUFACTURER PART") "0805W8F2200T5E"))
      (libsource (lib "altium-import") (part "root_0_220_"))
    )
    (comp (ref "R60")
      (value "10K")
      (footprint "R0603")
      (fields (field (name "MANUFACTURER") "UniOhm") (field (name "MANUFACTURER PART") "0603WAF1002T5E"))
      (libsource (lib "altium-import") (part "root_0_10K_"))
    )
    (comp (ref "R61")
      (value "330")
      (footprint "R0805")
      (fields (field (name "MANUFACTURER") "UniOhm") (field (name "MANUFACTURER PART") "0805W8F3300T5E"))
      (libsource (lib "altium-import") (part "root_1_330_"))
    )
    (comp (ref "R62")
      (value "10K")
      (footprint "R0805")
      (fields (field (name "MANUFACTURER") "UniOhm") (field (name "MANUFACTURER PART") "0805W8F1002T5E"))
      (libsource (lib "altium-import") (part "root_2_10K_"))
    )
    (comp (ref "R63")
      (value "10K")
      (footprint "R0805")
      (fields (field (name "MANUFACTURER") "UniOhm") (field (name "MANUFACTURER PART") "0805W8F1002T5E"))
      (libsource (lib "altium-import") (part "root_2_10K_"))
    )
    (comp (ref "R64")
      (value "10K")
      (footprint "R0805")
      (fields (field (name "MANUFACTURER") "UniOhm") (field (name "MANUFACTURER PART") "0805W8F1002T5E"))
      (libsource (lib "altium-import") (part "root_2_10K_"))
    )
    (comp (ref "R65")
      (value "10K")
      (footprint "R0805")
      (fields (field (name "MANUFACTURER") "UniOhm") (field (name "MANUFACTURER PART") "0805W8F1002T5E"))
      (libsource (lib "altium-import") (part "root_2_10K_"))
    )
    (comp (ref "RC1")
      (value "Header-Male-2.54_1x3")
      (footprint "HDR-TH_3P-P2.54-V-M-1")
      (fields (field (name "MANUFACTURER") "BOOMELE") (field (name "MANUFACTURER PART") "Header2.54mm 1*3P"))
      (libsource (lib "altium-import") (part "root_0_Header-Male-2.54_1x3_"))
    )
    (comp (ref "RC2")
      (value "Header-Male-2.54_1x3")
      (footprint "HDR-TH_3P-P2.54-V-M-1")
      (fields (field (name "MANUFACTURER") "BOOMELE") (field (name "MANUFACTURER PART") "Header2.54mm 1*3P"))
      (libsource (lib "altium-import") (part "root_0_Header-Male-2.54_1x3_"))
    )
    (comp (ref "RC3")
      (value "Header-Male-2.54_1x3")
      (footprint "HDR-TH_3P-P2.54-V-M-1")
      (fields (field (name "MANUFACTURER") "BOOMELE") (field (name "MANUFACTURER PART") "Header2.54mm 1*3P"))
      (libsource (lib "altium-import") (part "root_0_Header-Male-2.54_1x3_"))
    )
    (comp (ref "RC4")
      (value "Header-Male-2.54_1x3")
      (footprint "HDR-TH_3P-P2.54-V-M-1")
      (fields (field (name "MANUFACTURER") "BOOMELE") (field (name "MANUFACTURER PART") "Header2.54mm 1*3P"))
      (libsource (lib "altium-import") (part "root_0_Header-Male-2.54_1x3_"))
    )
    (comp (ref "SIGNAL")
      (value "DB128L-5.08-3P")
      (footprint "CONN-TH_DB128L-5.08-3P")
      (fields (field (name "MANUFACTURER") "DIBO") (field (name "CONTRIBUTOR") "LCSC"))
      (libsource (lib "altium-import") (part "root_0_DB128L-5.08-3P_"))
    )
    (comp (ref "SPEED")
      (value "DB128L-5.08-3P")
      (footprint "CONN-TH_DB128L-5.08-3P")
      (fields (field (name "MANUFACTURER") "DIBO") (field (name "CONTRIBUTOR") "LCSC"))
      (libsource (lib "altium-import") (part "root_0_DB128L-5.08-3P_"))
    )
    (comp (ref "U1")
      (value "CBMUD1200HAS8")
      (footprint "SOIC-8_L4.9-W3.9-P1.27-LS6.0-BL")
      (fields
        (field (name "MANUFACTURER") "Corebai(芯佰微)")
        (field (name "MANUFACTURER PART") "CBMuD1200HAS8")
        (field (name "CONTRIBUTOR") "LCSC")
      )
      (libsource (lib "altium-import") (part "root_0_CBMUD1200HAS8_"))
    )
    (comp (ref "U2")
      (value "TPS5430DDAR")
      (footprint "SOIC-8_L5.0-W4.0-P1.27-LS6.0-BL-EP2.0")
      (fields (field (name "MANUFACTURER") "TI"))
      (libsource (lib "altium-import") (part "root_0_TPS5430DDAR_"))
    )
    (comp (ref "U3")
      (value "74AHCT595D,118")
      (footprint "SOP-16_L10.0-W3.9-P1.27-LS6.0-BL")
      (fields (field (name "MANUFACTURER") "Nexperia") (field (name "CONTRIBUTOR") "LCSC"))
      (libsource (lib "altium-import") (part "root_0_74AHCT595D,118_"))
    )
    (comp (ref "U4")
      (value "74AHCT595D,118")
      (footprint "SOP-16_L10.0-W3.9-P1.27-LS6.0-BL")
      (fields (field (name "MANUFACTURER") "Nexperia") (field (name "CONTRIBUTOR") "LCSC"))
      (libsource (lib "altium-import") (part "root_0_74AHCT595D,118_"))
    )
    (comp (ref "U5")
      (value "74AHCT595D,118")
      (footprint "SOP-16_L10.0-W3.9-P1.27-LS6.0-BL")
      (fields (field (name "MANUFACTURER") "Nexperia") (field (name "CONTRIBUTOR") "LCSC"))
      (libsource (lib "altium-import") (part "root_0_74AHCT595D,118_"))
    )
    (comp (ref "U6")
      (value "LM358DR2G")
      (footprint "SOIC-8_L5.0-W4.0-P1.27-LS6.0-BL")
      (fields (field (name "MANUFACTURER") "ON"))
      (libsource (lib "altium-import") (part "root_0_LM358DR2G_"))
    )
    (comp (ref "U7")
      (value "EL817S1(C)(TU)-F")
      (footprint "OPTO-SMD-4_L4.6-W6.5-P2.54-LS10.3-TL")
      (fields (field (name "MANUFACTURER") "EVERLIGHT"))
      (libsource (lib "altium-import") (part "root_0_EL817S1(C)(TU)-F_"))
    )
    (comp (ref "U8")
      (value "EL817S1(C)(TU)-F")
      (footprint "OPTO-SMD-4_L4.6-W6.5-P2.54-LS10.3-TL")
      (fields (field (name "MANUFACTURER") "EVERLIGHT"))
      (libsource (lib "altium-import") (part "root_0_EL817S1(C)(TU)-F_"))
    )
    (comp (ref "U9")
      (value "SilentStepStick_TMC5160_V1.4")
      (footprint "SILENTSTEPSTICK_TMC5160")
      (fields (field (name "CONTRIBUTOR") "philipp.maack"))
      (libsource (lib "altium-import") (part "root_0_SilentStepStick_TMC5160_V1.4_"))
    )
    (comp (ref "U10")
      (value "SilentStepStick_TMC5160_V1.4")
      (footprint "SILENTSTEPSTICK_TMC5160")
      (fields (field (name "CONTRIBUTOR") "philipp.maack"))
      (libsource (lib "altium-import") (part "root_0_SilentStepStick_TMC5160_V1.4_"))
    )
    (comp (ref "U11")
      (value "SilentStepStick_TMC5160_V1.4")
      (footprint "SILENTSTEPSTICK_TMC5160")
      (fields (field (name "CONTRIBUTOR") "philipp.maack"))
      (libsource (lib "altium-import") (part "root_0_SilentStepStick_TMC5160_V1.4_"))
    )
    (comp (ref "U12")
      (value "SilentStepStick_TMC5160_V1.4")
      (footprint "SILENTSTEPSTICK_TMC5160")
      (fields (field (name "CONTRIBUTOR") "philipp.maack"))
      (libsource (lib "altium-import") (part "root_0_SilentStepStick_TMC5160_V1.4_"))
    )
    (comp (ref "U14")
      (value "74LVC2G17GV,125")
      (footprint "SC-74-6_L3.0-W1.5-P0.95-LS2.8-BL")
      (fields (field (name "MANUFACTURER") "Nexperia") (field (name "CONTRIBUTOR") "LCSC"))
      (libsource (lib "altium-import") (part "root_0_74LVC2G17GV,125_"))
    )
    (comp (ref "U15")
      (value "CBMUD1200HAS8")
      (footprint "SOIC-8_L4.9-W3.9-P1.27-LS6.0-BL")
      (fields
        (field (name "MANUFACTURER") "Corebai(芯佰微)")
        (field (name "MANUFACTURER PART") "CBMuD1200HAS8")
        (field (name "CONTRIBUTOR") "LCSC")
      )
      (libsource (lib "altium-import") (part "root_0_CBMUD1200HAS8_"))
    )
    (comp (ref "U16")
      (value "CBMUD1200HAS8")
      (footprint "SOIC-8_L4.9-W3.9-P1.27-LS6.0-BL")
      (fields
        (field (name "MANUFACTURER") "Corebai(芯佰微)")
        (field (name "MANUFACTURER PART") "CBMuD1200HAS8")
        (field (name "CONTRIBUTOR") "LCSC")
      )
      (libsource (lib "altium-import") (part "root_0_CBMUD1200HAS8_"))
    )
    (comp (ref "U17")
      (value "CBMUD1200HAS8")
      (footprint "SOIC-8_L4.9-W3.9-P1.27-LS6.0-BL")
      (fields
        (field (name "MANUFACTURER") "Corebai(芯佰微)")
        (field (name "MANUFACTURER PART") "CBMuD1200HAS8")
        (field (name "CONTRIBUTOR") "LCSC")
      )
      (libsource (lib "altium-import") (part "root_0_CBMUD1200HAS8_"))
    )
    (comp (ref "U18")
      (value "CBMUD1200HAS8")
      (footprint "SOIC-8_L4.9-W3.9-P1.27-LS6.0-BL")
      (fields
        (field (name "MANUFACTURER") "Corebai(芯佰微)")
        (field (name "MANUFACTURER PART") "CBMuD1200HAS8")
        (field (name "CONTRIBUTOR") "LCSC")
      )
      (libsource (lib "altium-import") (part "root_0_CBMUD1200HAS8_"))
    )
    (comp (ref "U19")
      (value "74LVC2G17GV,125")
      (footprint "SC-74-6_L3.0-W1.5-P0.95-LS2.8-BL")
      (fields (field (name "MANUFACTURER") "Nexperia") (field (name "CONTRIBUTOR") "LCSC"))
      (libsource (lib "altium-import") (part "root_0_74LVC2G17GV,125_"))
    )
    (comp (ref "U20")
      (value "B0505S-1W_C882272")
      (footprint "PWRM-TH_BXXXXS-1WR3")
      (fields
        (field (name "MANUFACTURER") "VISOM")
        (field (name "MANUFACTURER PART") "B0505S-1W")
        (field (name "CONTRIBUTOR") "LCSC")
      )
      (libsource (lib "altium-import") (part "root_0_B0505S-1W_C882272_"))
    )
    (comp (ref "U26")
      (value "ESP32-WROOM-32D(16MB)")
      (footprint "WIFIM-SMD_39P-L25.5-W18.0-P1.27-BL")
      (fields (field (name "MANUFACTURER") "Espressif Systems") (field (name "CONTRIBUTOR") "LCSC"))
      (libsource (lib "altium-import") (part "root_0_ESP32-WROOM-32D(16MB)_"))
    )
    (comp (ref "U28")
      (value "AMS1117-3.3")
      (footprint "SOT-223-3_L6.5-W3.4-P2.30-LS7.0-BR")
      (fields (field (name "MANUFACTURER") "AMS"))
      (libsource (lib "altium-import") (part "root_0_AMS1117-3.3_"))
    )
    (comp (ref "U29")
      (value "CP2102-GMR")
      (footprint "QFN-28_L5.0-W5.0-P0.50-BL-EP")
      (fields (field (name "MANUFACTURER") "SILICON LABS"))
      (libsource (lib "altium-import") (part "root_0_CP2102-GMR_"))
    )
    (comp (ref "USB1")
      (value "micro USBFemale")
      (footprint "MICRO-USB-SMD_5P-P0.65-H-F_C10418")
      (fields (field (name "MANUFACTURER") "ValuePro"))
      (libsource (lib "altium-import") (part "root_0_micro USBFemale_"))
    )
    (comp (ref "X_MOTOR")
      (value "DB128L-5.08-4P-GN-S")
      (footprint "CONN-TH_4P-5.00_DB128L-5.0-4P-BU-S")
      (fields (field (name "MANUFACTURER") "DIBO") (field (name "CONTRIBUTOR") "LCSC"))
      (libsource (lib "") (part "root_0_DB128L-5.08-4P-GN-S__1"))
    )
    (comp (ref "Y_MOTOR")
      (value "DB128L-5.08-4P-GN-S")
      (footprint "CONN-TH_4P-5.00_DB128L-5.0-4P-BU-S")
      (fields (field (name "MANUFACTURER") "DIBO") (field (name "CONTRIBUTOR") "LCSC"))
      (libsource (lib "") (part "root_0_DB128L-5.08-4P-GN-S__1"))
    )
    (comp (ref "Z_MOTOR")
      (value "DB128L-5.08-4P-GN-S")
      (footprint "CONN-TH_4P-5.00_DB128L-5.0-4P-BU-S")
      (fields (field (name "MANUFACTURER") "DIBO") (field (name "CONTRIBUTOR") "LCSC"))
      (libsource (lib "") (part "root_0_DB128L-5.08-4P-GN-S__1"))
    )
  )
  (nets
    (net (code "1") (name "+3V3") (class "Default")
      (node (ref "C1") (pin "2") (pinfunction "2_2") (pintype "passive"))
      (node (ref "C2") (pin "2") (pinfunction "2_2") (pintype "passive"))
      (node (ref "C35") (pin "2") (pinfunction "2_2") (pintype "passive"))
      (node (ref "C36") (pin "2") (pinfunction "2_2") (pintype "passive"))
      (node (ref "C42") (pin "2") (pinfunction "2_2") (pintype "passive"))
      (node (ref "C43") (pin "2") (pinfunction "2_2") (pintype "passive"))
      (node (ref "C47") (pin "2") (pinfunction "2_2") (pintype "passive"))
      (node (ref "C48") (pin "2") (pinfunction "2_2") (pintype "passive"))
      (node (ref "C52") (pin "2") (pinfunction "2_2") (pintype "passive"))
      (node (ref "JP9") (pin "1") (pinfunction "1_1") (pintype "passive"))
      (node (ref "MICROSD") (pin "4") (pinfunction "VDD_4") (pintype "passive"))
      (node (ref "R55") (pin "2") (pinfunction "2_2") (pintype "passive"))
      (node (ref "U1") (pin "8") (pinfunction "VDD2_8") (pintype "passive"))
      (node (ref "U15") (pin "8") (pinfunction "VDD2_8") (pintype "passive"))
      (node (ref "U16") (pin "8") (pinfunction "VDD2_8") (pintype "passive"))
      (node (ref "U26") (pin "2") (pinfunction "VDD33_2") (pintype "passive"))
      (node (ref "U28") (pin "2") (pinfunction "Vout_2") (pintype "passive"))
      (node (ref "U28") (pin "4") (pinfunction "Vout_4") (pintype "passive"))
    )
    (net (code "2") (name "+5V") (class "Default")
      (node (ref "C23") (pin "2") (pinfunction "2_2") (pintype "passive"))
      (node (ref "C7") (pin "1") (pinfunction "1_1") (pintype "passive"))
      (node (ref "C8") (pin "2") (pinfunction "2_2") (pintype "passive"))
      (node (ref "C9") (pin "2") (pinfunction "2_2") (pintype "passive"))
      (node (ref "D10") (pin "1") (pinfunction "A_1") (pintype "passive"))
      (node (ref "JP10") (pin "1") (pinfunction "1_1") (pintype "passive"))
      (node (ref "JP28") (pin "2") (pinfunction "2_2") (pintype "passive"))
      (node (ref "L1") (pin "2") (pinfunction "2_2") (pintype "passive"))
      (node (ref "R2") (pin "1") (pinfunction "1_1") (pintype "passive"))
      (node (ref "R3") (pin "2") (pinfunction "2_2") (pintype "passive"))
      (node (ref "RC1") (pin "2") (pinfunction "2_2") (pintype "passive"))
      (node (ref "RC2") (pin "2") (pinfunction "2_2") (pintype "passive"))
      (node (ref "RC3") (pin "2") (pinfunction "2_2") (pintype "passive"))
      (node (ref "RC4") (pin "2") (pinfunction "2_2") (pintype "passive"))
      (node (ref "U20") (pin "2") (pinfunction "Vin_2") (pintype "passive"))
    )
    (net (code "3") (name "+5V_ISO") (class "Default")
      (node (ref "C24") (pin "2") (pinfunction "2_2") (pintype "passive"))
      (node (ref "C27") (pin "2") (pinfunction "2_2") (pintype "passive"))
      (node (ref "C28") (pin "2") (pinfunction "2_2") (pintype "passive"))
      (node (ref "C44") (pin "2") (pinfunction "2_2") (pintype "passive"))
      (node (ref "C51") (pin "2") (pinfunction "2_2") (pintype "passive"))
      (node (ref "C55") (pin "2") (pinfunction "2_2") (pintype "passive"))
      (node (ref "INPUT_1") (pin "1") (pinfunction "1_1") (pintype "passive"))
      (node (ref "INPUT_2") (pin "1") (pinfunction "1_1") (pintype "passive"))
      (node (ref "INPUT_3") (pin "1") (pinfunction "1_1") (pintype "passive"))
      (node (ref "R18") (pin "2") (pinfunction "2_2") (pintype "passive"))
      (node (ref "U1") (pin "1") (pinfunction "VDD1_1") (pintype "passive"))
      (node (ref "U14") (pin "5") (pinfunction "VCC_5") (pintype "passive"))
      (node (ref "U15") (pin "1") (pinfunction "VDD1_1") (pintype "passive"))
      (node (ref "U16") (pin "1") (pinfunction "VDD1_1") (pintype "passive"))
      (node (ref "U17") (pin "8") (pinfunction "VDD2_8") (pintype "passive"))
      (node (ref "U18") (pin "8") (pinfunction "VDD2_8") (pintype "passive"))
      (node (ref "U19") (pin "5") (pinfunction "VCC_5") (pintype "passive"))
      (node (ref "U20") (pin "4") (pinfunction "Vo_4") (pintype "passive"))
    )
    (net (code "4") (name "/A_CS") (class "Default")
      (node (ref "U10") (pin "4") (pinfunction "CS_4") (pintype "passive"))
      (node (ref "U4") (pin "3") (pinfunction "Q3_3") (pintype "passive"))
    )
    (net (code "5") (name "/A_DIAG") (class "Default")
      (node (ref "R54") (pin "2") (pinfunction "2_2") (pintype "passive"))
      (node (ref "U26") (pin "7") (pinfunction "IO35_7") (pintype "passive"))
    )
    (net (code "6") (name "/A_Dir") (class "Default")
      (node (ref "JP25") (pin "2") (pinfunction "2_2") (pintype "passive"))
      (node (ref "U10") (pin "8") (pinfunction "DIR_8") (pintype "passive"))
      (node (ref "U4") (pin "1") (pinfunction "Q1_1") (pintype "passive"))
    )
    (net (code "7") (name "/A_En") (class "Default")
      (node (ref "JP23") (pin "2") (pinfunction "2_2") (pintype "passive"))
      (node (ref "U10") (pin "1") (pinfunction "EN_1") (pintype "passive"))
      (node (ref "U4") (pin "15") (pinfunction "Q0_15") (pintype "passive"))
    )
    (net (code "8") (name "/A_Step") (class "Default")
      (node (ref "JP24") (pin "2") (pinfunction "2_2") (pintype "passive"))
      (node (ref "U10") (pin "7") (pinfunction "STEP_7") (pintype "passive"))
      (node (ref "U4") (pin "2") (pinfunction "Q2_2") (pintype "passive"))
    )
    (net (code "9") (name "/CS_SD") (class "Default")
      (node (ref "MICROSD") (pin "2") (pinfunction "CDDAT3(CS)_2") (pintype "passive"))
      (node (ref "U26") (pin "29") (pinfunction "IO5_29") (pintype "passive"))
    )
    (net (code "10") (name "/DC") (class "Default")
      (node (ref "D6") (pin "2") (pinfunction "K_2") (pintype "passive"))
      (node (ref "Q5") (pin "2") (pinfunction "D_2") (pintype "passive"))
      (node (ref "SPEED") (pin "2") (pinfunction "2_2") (pintype "passive"))
    )
    (net (code "11") (name "/DTR") (class "Default")
      (node (ref "Q10") (pin "2") (pinfunction "E_2") (pintype "passive"))
      (node (ref "R19") (pin "2") (pinfunction "2_2") (pintype "passive"))
      (node (ref "U29") (pin "28") (pinfunction "DTR_28") (pintype "passive"))
    )
    (net (code "12") (name "/ESPRX") (class "Default")
      (node (ref "U26") (pin "34") (pinfunction "RXD0_34") (pintype "passive"))
      (node (ref "U29") (pin "26") (pinfunction "TXD_26") (pintype "passive"))
    )
    (net (code "13") (name "/ESPTX") (class "Default")
      (node (ref "U26") (pin "35") (pinfunction "TXD0_35") (pintype "passive"))
      (node (ref "U29") (pin "25") (pinfunction "RXD_25") (pintype "passive"))
    )
    (net (code "14") (name "/FAN") (class "Default")
      (node (ref "Q7") (pin "1") (pinfunction "G_1") (pintype "passive"))
      (node (ref "U26") (pin "13") (pinfunction "IO14_13") (pintype "passive"))
    )
    (net (code "15") (name "/GPIO0") (class "Default")
      (node (ref "JP34") (pin "2") (pinfunction "2_2") (pintype "passive"))
      (node (ref "Q10") (pin "3") (pinfunction "C_3") (pintype "passive"))
      (node (ref "U26") (pin "25") (pinfunction "IO0_25") (pintype "passive"))
    )
    (net (code "16") (name "/I2SO16") (class "Default")
      (node (ref "R14") (pin "1") (pinfunction "1_1") (pintype "passive"))
      (node (ref "U5") (pin "15") (pinfunction "Q0_15") (pintype "passive"))
    )
    (net (code "17") (name "/I2SO17") (class "Default")
      (node (ref "R15") (pin "1") (pinfunction "1_1") (pintype "passive"))
      (node (ref "U5") (pin "1") (pinfunction "Q1_1") (pintype "passive"))
    )
    (net (code "18") (name "/I2SO18") (class "Default")
      (node (ref "U18") (pin "2") (pinfunction "VIA_2") (pintype "passive"))
      (node (ref "U5") (pin "2") (pinfunction "Q2_2") (pintype "passive"))
    )
    (net (code "19") (name "/I2SO19") (class "Default")
      (node (ref "U18") (pin "3") (pinfunction "VIB_3") (pintype "passive"))
      (node (ref "U5") (pin "3") (pinfunction "Q3_3") (pintype "passive"))
    )
    (net (code "20") (name "/I2SO20") (class "Default")
      (node (ref "U17") (pin "2") (pinfunction "VIA_2") (pintype "passive"))
      (node (ref "U5") (pin "4") (pinfunction "Q4_4") (pintype "passive"))
    )
    (net (code "21") (name "/I2SO21") (class "Default")
      (node (ref "U17") (pin "3") (pinfunction "VIB_3") (pintype "passive"))
      (node (ref "U5") (pin "5") (pinfunction "Q5_5") (pintype "passive"))
    )
    (net (code "22") (name "/I2SO22") (class "Default")
      (node (ref "Q4") (pin "1") (pinfunction "G_1") (pintype "passive"))
      (node (ref "U5") (pin "6") (pinfunction "Q6_6") (pintype "passive"))
    )
    (net (code "23") (name "/I2SO23") (class "Default")
      (node (ref "Q3") (pin "1") (pinfunction "G_1") (pintype "passive"))
      (node (ref "U5") (pin "7") (pinfunction "Q7_7") (pintype "passive"))
    )
    (net (code "24") (name "/I2S_BCK") (class "Default")
      (node (ref "R8") (pin "1") (pinfunction "1_1") (pintype "passive"))
      (node (ref "U26") (pin "36") (pinfunction "IO22_36") (pintype "passive"))
      (node (ref "U3") (pin "11") (pinfunction "SHCP_11") (pintype "passive"))
      (node (ref "U4") (pin "11") (pinfunction "SHCP_11") (pintype "passive"))
      (node (ref "U5") (pin "11") (pinfunction "SHCP_11") (pintype "passive"))
    )
    (net (code "25") (name "/I2S_DATA") (class "Default")
      (node (ref "U26") (pin "33") (pinfunction "IO21_33") (pintype "passive"))
      (node (ref "U3") (pin "14") (pinfunction "DS_14") (pintype "passive"))
    )
    (net (code "26") (name "/I2S_WS") (class "Default")
      (node (ref "U26") (pin "28") (pinfunction "IO17_28") (pintype "passive"))
      (node (ref "U3") (pin "12") (pinfunction "STCP_12") (pintype "passive"))
      (node (ref "U4") (pin "12") (pinfunction "STCP_12") (pintype "passive"))
      (node (ref "U5") (pin "12") (pinfunction "STCP_12") (pintype "passive"))
    )
    (net (code "27") (name "/IN_1") (class "Default")
      (node (ref "U1") (pin "7") (pinfunction "VOA_7") (pintype "passive"))
      (node (ref "U26") (pin "26") (pinfunction "IO4_26") (pintype "passive"))
    )
    (net (code "28") (name "/IN_2") (class "Default")
      (node (ref "U1") (pin "6") (pinfunction "VOB_6") (pintype "passive"))
      (node (ref "U26") (pin "8") (pinfunction "IO32_8") (pintype "passive"))
    )
    (net (code "29") (name "/IN_3") (class "Default")
      (node (ref "U15") (pin "7") (pinfunction "VOA_7") (pintype "passive"))
      (node (ref "U26") (pin "9") (pinfunction "IO33_9") (pintype "passive"))
    )
    (net (code "30") (name "/IN_4") (class "Default")
      (node (ref "U15") (pin "6") (pinfunction "VOB_6") (pintype "passive"))
      (node (ref "U26") (pin "10") (pinfunction "IO25_10") (pintype "passive"))
    )
    (net (code "31") (name "/IN_5") (class "Default")
      (node (ref "U16") (pin "7") (pinfunction "VOA_7") (pintype "passive"))
      (node (ref "U26") (pin "11") (pinfunction "IO26_11") (pintype "passive"))
    )
    (net (code "32") (name "/IN_6") (class "Default")
      (node (ref "U16") (pin "6") (pinfunction "VOB_6") (pintype "passive"))
      (node (ref "U26") (pin "12") (pinfunction "IO27_12") (pintype "passive"))
    )
    (net (code "33") (name "/M0") (class "Default")
      (node (ref "JP11") (pin "2") (pinfunction "2_2") (pintype "passive"))
      (node (ref "JP12") (pin "2") (pinfunction "2_2") (pintype "passive"))
      (node (ref "JP30") (pin "2") (pinfunction "2_2") (pintype "passive"))
      (node (ref "U10") (pin "2") (pinfunction "SDI_2") (pintype "passive"))
      (node (ref "U11") (pin "2") (pinfunction "SDI_2") (pintype "passive"))
      (node (ref "U12") (pin "2") (pinfunction "SDI_2") (pintype "passive"))
      (node (ref "U9") (pin "2") (pinfunction "SDI_2") (pintype "passive"))
    )
    (net (code "34") (name "/M1") (class "Default")
      (node (ref "JP13") (pin "2") (pinfunction "2_2") (pintype "passive"))
      (node (ref "JP14") (pin "2") (pinfunction "2_2") (pintype "passive"))
      (node (ref "JP31") (pin "2") (pinfunction "2_2") (pintype "passive"))
      (node (ref "U10") (pin "3") (pinfunction "SCK_3") (pintype "passive"))
      (node (ref "U11") (pin "3") (pinfunction "SCK_3") (pintype "passive"))
      (node (ref "U12") (pin "3") (pinfunction "SCK_3") (pintype "passive"))
      (node (ref "U9") (pin "3") (pinfunction "SCK_3") (pintype "passive"))
    )
    (net (code "35") (name "/MISO") (class "Default")
      (node (ref "JP6") (pin "1") (pinfunction "1_1") (pintype "passive"))
      (node (ref "MICROSD") (pin "7") (pinfunction "DAT0(D0)_7") (pintype "passive"))
      (node (ref "U26") (pin "31") (pinfunction "IO19_31") (pintype "passive"))
    )
    (net (code "36") (name "/MOSI") (class "Default")
      (node (ref "JP12") (pin "1") (pinfunction "1_1") (pintype "passive"))
      (node (ref "MICROSD") (pin "3") (pinfunction "CMD(DI)_3") (pintype "passive"))
      (node (ref "U26") (pin "37") (pinfunction "IO23_37") (pintype "passive"))
    )
    (net (code "37") (name "/PWM") (class "Default")
      (node (ref "ESC") (pin "3") (pinfunction "3_3") (pintype "passive"))
      (node (ref "Q6") (pin "1") (pinfunction "G_1") (pintype "passive"))
      (node (ref "R10") (pin "1") (pinfunction "1_1") (pintype "passive"))
      (node (ref "R9") (pin "1") (pinfunction "1_1") (pintype "passive"))
      (node (ref "U26") (pin "27") (pinfunction "IO16_27") (pintype "passive"))
    )
    (net (code "38") (name "/RC1") (class "Default")
      (node (ref "R56") (pin "1") (pinfunction "1_1") (pintype "passive"))
      (node (ref "U26") (pin "24") (pinfunction "IO2_24") (pintype "passive"))
    )
    (net (code "39") (name "/RC2") (class "Default")
      (node (ref "R57") (pin "1") (pinfunction "1_1") (pintype "passive"))
      (node (ref "U26") (pin "23") (pinfunction "IO15_23") (pintype "passive"))
    )
    (net (code "40") (name "/RC3") (class "Default")
      (node (ref "R58") (pin "1") (pinfunction "1_1") (pintype "passive"))
      (node (ref "U26") (pin "16") (pinfunction "IO13_16") (pintype "passive"))
    )
    (net (code "41") (name "/RC4") (class "Default")
      (node (ref "R59") (pin "1") (pinfunction "1_1") (pintype "passive"))
      (node (ref "U26") (pin "14") (pinfunction "IO12_14") (pintype "passive"))
    )
    (net (code "42") (name "/RESET") (class "Default")
      (node (ref "C41") (pin "2") (pinfunction "2_2") (pintype "passive"))
      (node (ref "JP33") (pin "2") (pinfunction "2_2") (pintype "passive"))
      (node (ref "Q9") (pin "3") (pinfunction "C_3") (pintype "passive"))
      (node (ref "R55") (pin "1") (pinfunction "1_1") (pintype "passive"))
      (node (ref "U26") (pin "3") (pinfunction "EN_3") (pintype "passive"))
    )
    (net (code "43") (name "/RTS") (class "Default")
      (node (ref "Q9") (pin "2") (pinfunction "E_2") (pintype "passive"))
      (node (ref "R20") (pin "1") (pinfunction "1_1") (pintype "passive"))
      (node (ref "U29") (pin "24") (pinfunction "RTS_24") (pintype "passive"))
    )
    (net (code "44") (name "/SCK") (class "Default")
      (node (ref "JP14") (pin "1") (pinfunction "1_1") (pintype "passive"))
      (node (ref "MICROSD") (pin "5") (pinfunction "CLK(SCLK)_5") (pintype "passive"))
      (node (ref "U26") (pin "30") (pinfunction "IO18_30") (pintype "passive"))
    )
    (net (code "45") (name "/SCommon") (class "Default")
      (node (ref "SIGNAL") (pin "3") (pinfunction "3_3") (pintype "passive"))
      (node (ref "U7") (pin "3") (pinfunction "EM_3") (pintype "passive"))
      (node (ref "U8") (pin "3") (pinfunction "EM_3") (pintype "passive"))
    )
    (net (code "46") (name "/SOUT1") (class "Default")
      (node (ref "SIGNAL") (pin "2") (pinfunction "2_2") (pintype "passive"))
      (node (ref "U8") (pin "4") (pinfunction "COL_4") (pintype "passive"))
    )
    (net (code "47") (name "/SOUT2") (class "Default")
      (node (ref "SIGNAL") (pin "1") (pinfunction "1_1") (pintype "passive"))
      (node (ref "U7") (pin "4") (pinfunction "COL_4") (pintype "passive"))
    )
    (net (code "48") (name "/Step_Reset") (class "Default")
      (node (ref "JP32") (pin "2") (pinfunction "2_2") (pintype "passive"))
      (node (ref "JP5") (pin "2") (pinfunction "2_2") (pintype "passive"))
      (node (ref "JP6") (pin "2") (pinfunction "2_2") (pintype "passive"))
      (node (ref "U10") (pin "5") (pinfunction "SDO_5") (pintype "passive"))
      (node (ref "U11") (pin "5") (pinfunction "SDO_5") (pintype "passive"))
      (node (ref "U12") (pin "5") (pinfunction "SDO_5") (pintype "passive"))
      (node (ref "U9") (pin "5") (pinfunction "SDO_5") (pintype "passive"))
    )
    (net (code "49") (name "/Step_Sleep") (class "Default")
      (node (ref "JP7") (pin "2") (pinfunction "2_2") (pintype "passive"))
      (node (ref "JP8") (pin "2") (pinfunction "2_2") (pintype "passive"))
      (node (ref "U10") (pin "6") (pinfunction "DCO_6") (pintype "passive"))
      (node (ref "U11") (pin "6") (pinfunction "DCO_6") (pintype "passive"))
      (node (ref "U12") (pin "6") (pinfunction "DCO_6") (pintype "passive"))
      (node (ref "U9") (pin "6") (pinfunction "DCO_6") (pintype "passive"))
    )
    (net (code "50") (name "/V0-10") (class "Default")
      (node (ref "R11") (pin "2") (pinfunction "2_2") (pintype "passive"))
      (node (ref "SPEED") (pin "1") (pinfunction "1_1") (pintype "passive"))
      (node (ref "U6") (pin "1") (pinfunction "1OUT_1") (pintype "passive"))
    )
    (net (code "51") (name "/X_CS") (class "Default")
      (node (ref "U11") (pin "4") (pinfunction "CS_4") (pintype "passive"))
      (node (ref "U3") (pin "7") (pinfunction "Q7_7") (pintype "passive"))
    )
    (net (code "52") (name "/X_DIAG") (class "Default")
      (node (ref "R61") (pin "2") (pinfunction "2_2") (pintype "passive"))
      (node (ref "U26") (pin "4") (pinfunction "SENSOR_VP_4") (pintype "passive"))
    )
    (net (code "53") (name "/X_Dir") (class "Default")
      (node (ref "JP3") (pin "2") (pinfunction "2_2") (pintype "passive"))
      (node (ref "U11") (pin "8") (pinfunction "DIR_8") (pintype "passive"))
      (node (ref "U3") (pin "5") (pinfunction "Q5_5") (pintype "passive"))
    )
    (net (code "54") (name "/X_En") (class "Default")
      (node (ref "JP4") (pin "2") (pinfunction "2_2") (pintype "passive"))
      (node (ref "U11") (pin "1") (pinfunction "EN_1") (pintype "passive"))
      (node (ref "U3") (pin "4") (pinfunction "Q4_4") (pintype "passive"))
    )
    (net (code "55") (name "/X_Step") (class "Default")
      (node (ref "JP2") (pin "2") (pinfunction "2_2") (pintype "passive"))
      (node (ref "U11") (pin "7") (pinfunction "STEP_7") (pintype "passive"))
      (node (ref "U3") (pin "6") (pinfunction "Q6_6") (pintype "passive"))
    )
    (net (code "56") (name "/Y_CS") (class "Default")
      (node (ref "U3") (pin "3") (pinfunction "Q3_3") (pintype "passive"))
      (node (ref "U9") (pin "4") (pinfunction "CS_4") (pintype "passive"))
    )
    (net (code "57") (name "/Y_DIAG") (class "Default")
      (node (ref "R53") (pin "2") (pinfunction "2_2") (pintype "passive"))
      (node (ref "U26") (pin "5") (pinfunction "SENSOR_VN_5") (pintype "passive"))
    )
    (net (code "58") (name "/Y_Dir") (class "Default")
      (node (ref "JP21") (pin "2") (pinfunction "2_2") (pintype "passive"))
      (node (ref "U3") (pin "1") (pinfunction "Q1_1") (pintype "passive"))
      (node (ref "U9") (pin "8") (pinfunction "DIR_8") (pintype "passive"))
    )
    (net (code "59") (name "/Y_En") (class "Default")
      (node (ref "JP19") (pin "2") (pinfunction "2_2") (pintype "passive"))
      (node (ref "U3") (pin "15") (pinfunction "Q0_15") (pintype "passive"))
      (node (ref "U9") (pin "1") (pinfunction "EN_1") (pintype "passive"))
    )
    (net (code "60") (name "/Y_Step") (class "Default")
      (node (ref "JP20") (pin "2") (pinfunction "2_2") (pintype "passive"))
      (node (ref "U3") (pin "2") (pinfunction "Q2_2") (pintype "passive"))
      (node (ref "U9") (pin "7") (pinfunction "STEP_7") (pintype "passive"))
    )
    (net (code "61") (name "/Z_CS") (class "Default")
      (node (ref "U12") (pin "4") (pinfunction "CS_4") (pintype "passive"))
      (node (ref "U4") (pin "7") (pinfunction "Q7_7") (pintype "passive"))
    )
    (net (code "62") (name "/Z_DIAG") (class "Default")
      (node (ref "R52") (pin "2") (pinfunction "2_2") (pintype "passive"))
      (node (ref "U26") (pin "6") (pinfunction "IO34_6") (pintype "passive"))
    )
    (net (code "63") (name "/Z_Dir") (class "Default")
      (node (ref "JP17") (pin "2") (pinfunction "2_2") (pintype "passive"))
      (node (ref "U12") (pin "8") (pinfunction "DIR_8") (pintype "passive"))
      (node (ref "U4") (pin "5") (pinfunction "Q5_5") (pintype "passive"))
    )
    (net (code "64") (name "/Z_En") (class "Default")
      (node (ref "JP15") (pin "2") (pinfunction "2_2") (pintype "passive"))
      (node (ref "U12") (pin "1") (pinfunction "EN_1") (pintype "passive"))
      (node (ref "U4") (pin "4") (pinfunction "Q4_4") (pintype "passive"))
    )
    (net (code "65") (name "/Z_Step") (class "Default")
      (node (ref "JP16") (pin "2") (pinfunction "2_2") (pintype "passive"))
      (node (ref "U12") (pin "7") (pinfunction "STEP_7") (pintype "passive"))
      (node (ref "U4") (pin "6") (pinfunction "Q6_6") (pintype "passive"))
    )
    (net (code "66") (name "GND") (class "Default")
      (node (ref "C1") (pin "1") (pinfunction "1_1") (pintype "passive"))
      (node (ref "C10") (pin "1") (pinfunction "1_1") (pintype "passive"))
      (node (ref "C11") (pin "1") (pinfunction "1_1") (pintype "passive"))
      (node (ref "C12") (pin "1") (pinfunction "1_1") (pintype "passive"))
      (node (ref "C13") (pin "1") (pinfunction "1_1") (pintype "passive"))
      (node (ref "C14") (pin "1") (pinfunction "1_1") (pintype "passive"))
      (node (ref "C15") (pin "1") (pinfunction "1_1") (pintype "passive"))
      (node (ref "C16") (pin "2") (pinfunction "2_2") (pintype "passive"))
      (node (ref "C17") (pin "2") (pinfunction "2_2") (pintype "passive"))
      (node (ref "C18") (pin "1") (pinfunction "1_1") (pintype "passive"))
      (node (ref "C19") (pin "1") (pinfunction "1_1") (pintype "passive"))
      (node (ref "C2") (pin "1") (pinfunction "1_1") (pintype "passive"))
      (node (ref "C20") (pin "2") (pinfunction "2_2") (pintype "passive"))
      (node (ref "C21") (pin "2") (pinfunction "2_2") (pintype "passive"))
      (node (ref "C22") (pin "1") (pinfunction "1_1") (pintype "passive"))
      (node (ref "C23") (pin "1") (pinfunction "1_1") (pintype "passive"))
      (node (ref "C25") (pin "1") (pinfunction "1_1") (pintype "passive"))
      (node (ref "C26") (pin "1") (pinfunction "1_1") (pintype "passive"))
      (node (ref "C35") (pin "1") (pinfunction "1_1") (pintype "passive"))
      (node (ref "C36") (pin "1") (pinfunction "1_1") (pintype "passive"))
      (node (ref "C37") (pin "1") (pinfunction "1_1") (pintype "passive"))
      (node (ref "C38") (pin "1") (pinfunction "1_1") (pintype "passive"))
      (node (ref "C39") (pin "1") (pinfunction "1_1") (pintype "passive"))
      (node (ref "C4") (pin "1") (pinfunction "1_1") (pintype "passive"))
      (node (ref "C40") (pin "1") (pinfunction "1_1") (pintype "passive"))
      (node (ref "C41") (pin "1") (pinfunction "1_1") (pintype "passive"))
      (node (ref "C42") (pin "1") (pinfunction "1_1") (pintype "passive"))
      (node (ref "C43") (pin "1") (pinfunction "1_1") (pintype "passive"))
      (node (ref "C47") (pin "1") (pinfunction "1_1") (pintype "passive"))
      (node (ref "C48") (pin "1") (pinfunction "1_1") (pintype "passive"))
      (node (ref "C5") (pin "1") (pinfunction "1_1") (pintype "passive"))
      (node (ref "C52") (pin "1") (pinfunction "1_1") (pintype "passive"))
      (node (ref "C6") (pin "1") (pinfunction "1_1") (pintype "passive"))
      (node (ref "C7") (pin "2") (pinfunction "2_2") (pintype "passive"))
      (node (ref "C8") (pin "1") (pinfunction "1_1") (pintype "passive"))
      (node (ref "C9") (pin "1") (pinfunction "1_1") (pintype "passive"))
      (node (ref "D1") (pin "1") (pinfunction "1_1") (pintype "passive"))
      (node (ref "D11") (pin "1") (pinfunction "1_1") (pintype "passive"))
      (node (ref "D12") (pin "1") (pinfunction "1_1") (pintype "passive"))
      (node (ref "D2") (pin "1") (pinfunction "A_1") (pintype "passive"))
      (node (ref "D6") (pin "1") (pinfunction "A_1") (pintype "passive"))
      (node (ref "D7") (pin "1") (pinfunction "A_1") (pintype "passive"))
      (node (ref "D8") (pin "1") (pinfunction "A_1") (pintype "passive"))
      (node (ref "ESC") (pin "1") (pinfunction "1_1") (pintype "passive"))
      (node (ref "JP29") (pin "1") (pinfunction "1_1") (pintype "passive"))
      (node (ref "JP30") (pin "1") (pinfunction "1_1") (pintype "passive"))
      (node (ref "JP31") (pin "1") (pinfunction "1_1") (pintype "passive"))
      (node (ref "JP32") (pin "1") (pinfunction "1_1") (pintype "passive"))
      (node (ref "JP33") (pin "1") (pinfunction "1_1") (pintype "passive"))
      (node (ref "JP34") (pin "1") (pinfunction "1_1") (pintype "passive"))
      (node (ref "JP8") (pin "1") (pinfunction "1_1") (pintype "passive"))
      (node (ref "LED1") (pin "1") (pinfunction "K_1") (pintype "passive"))
      (node (ref "MICROSD") (pin "10") (pinfunction "GND_10") (pintype "passive"))
      (node (ref "MICROSD") (pin "11") (pinfunction "GND_11") (pintype "passive"))
      (node (ref "MICROSD") (pin "12") (pinfunction "GND_12") (pintype "passive"))
      (node (ref "MICROSD") (pin "13") (pinfunction "GND_13") (pintype "passive"))
      (node (ref "MICROSD") (pin "6") (pinfunction "VSS_6") (pintype "passive"))
      (node (ref "PWR") (pin "2") (pinfunction "2_2") (pintype "passive"))
      (node (ref "PWROUT1") (pin "2") (pinfunction "2_2") (pintype "passive"))
      (node (ref "PWROUT2") (pin "2") (pinfunction "2_2") (pintype "passive"))
      (node (ref "Q3") (pin "2") (pinfunction "S_2") (pintype "passive"))
      (node (ref "Q4") (pin "2") (pinfunction "S_2") (pintype "passive"))
      (node (ref "Q6") (pin "2") (pinfunction "S_2") (pintype "passive"))
      (node (ref "Q7") (pin "2") (pinfunction "S_2") (pintype "passive"))
      (node (ref "R1") (pin "2") (pinfunction "2_2") (pintype "passive"))
      (node (ref "R12") (pin "1") (pinfunction "1_1") (pintype "passive"))
      (node (ref "R57") (pin "2") (pinfunction "2_2") (pintype "passive"))
      (node (ref "R58") (pin "2") (pinfunction "2_2") (pintype "passive"))
      (node (ref "R8") (pin "2") (pinfunction "2_2") (pintype "passive"))
      (node (ref "R9") (pin "2") (pinfunction "2_2") (pintype "passive"))
      (node (ref "RC1") (pin "1") (pinfunction "1_1") (pintype "passive"))
      (node (ref "RC2") (pin "1") (pinfunction "1_1") (pintype "passive"))
      (node (ref "RC2") (pin "3") (pinfunction "3_3") (pintype "passive"))
      (node (ref "RC3") (pin "1") (pinfunction "1_1") (pintype "passive"))
      (node (ref "RC3") (pin "3") (pinfunction "3_3") (pintype "passive"))
      (node (ref "RC4") (pin "1") (pinfunction "1_1") (pintype "passive"))
      (node (ref "SPEED") (pin "3") (pinfunction "3_3") (pintype "passive"))
      (node (ref "U1") (pin "5") (pinfunction "GND2_5") (pintype "passive"))
      (node (ref "U10") (pin "10") (pinfunction "GND_10") (pintype "passive"))
      (node (ref "U10") (pin "16") (pinfunction "GND_16") (pintype "passive"))
      (node (ref "U11") (pin "10") (pinfunction "GND_10") (pintype "passive"))
      (node (ref "U11") (pin "16") (pinfunction "GND_16") (pintype "passive"))
      (node (ref "U12") (pin "10") (pinfunction "GND_10") (pintype "passive"))
      (node (ref "U12") (pin "16") (pinfunction "GND_16") (pintype "passive"))
      (node (ref "U15") (pin "5") (pinfunction "GND2_5") (pintype "passive"))
      (node (ref "U16") (pin "5") (pinfunction "GND2_5") (pintype "passive"))
      (node (ref "U17") (pin "4") (pinfunction "GND1_4") (pintype "passive"))
      (node (ref "U18") (pin "4") (pinfunction "GND1_4") (pintype "passive"))
      (node (ref "U2") (pin "6") (pinfunction "GND_6") (pintype "passive"))
      (node (ref "U2") (pin "9") (pinfunction "PowerPAD_9") (pintype "passive"))
      (node (ref "U20") (pin "1") (pinfunction "GND_1") (pintype "passive"))
      (node (ref "U26") (pin "1") (pinfunction "GND_1") (pintype "passive"))
      (node (ref "U26") (pin "15") (pinfunction "GND_15") (pintype "passive"))
      (node (ref "U26") (pin "38") (pinfunction "GND_38") (pintype "passive"))
      (node (ref "U26") (pin "39") (pinfunction "GND_39") (pintype "passive"))
      (node (ref "U28") (pin "1") (pinfunction "GND/ADJ_1") (pintype "passive"))
      (node (ref "U29") (pin "3") (pinfunction "GND_3") (pintype "passive"))
      (node (ref "U3") (pin "13") (pinfunction "OE#_13") (pintype "passive"))
      (node (ref "U3") (pin "8") (pinfunction "GND_8") (pintype "passive"))
      (node (ref "U4") (pin "13") (pinfunction "OE#_13") (pintype "passive"))
      (node (ref "U4") (pin "8") (pinfunction "GND_8") (pintype "passive"))
      (node (ref "U5") (pin "13") (pinfunction "OE#_13") (pintype "passive"))
      (node (ref "U5") (pin "8") (pinfunction "GND_8") (pintype "passive"))
      (node (ref "U6") (pin "4") (pinfunction "GND_4") (pintype "passive"))
      (node (ref "U7") (pin "2") (pinfunction "CAT_2") (pintype "passive"))
      (node (ref "U8") (pin "2") (pinfunction "CAT_2") (pintype "passive"))
      (node (ref "U9") (pin "10") (pinfunction "GND_10") (pintype "passive"))
      (node (ref "U9") (pin "16") (pinfunction "GND_16") (pintype "passive"))
      (node (ref "USB1") (pin "0") (pinfunction "MTN_0") (pintype "passive"))
      (node (ref "USB1") (pin "5") (pinfunction "V-_5") (pintype "passive"))
    )
    (net (code "67") (name "GND_ISO") (class "Default")
      (node (ref "C24") (pin "1") (pinfunction "1_1") (pintype "passive"))
      (node (ref "C27") (pin "1") (pinfunction "1_1") (pintype "passive"))
      (node (ref "C28") (pin "1") (pinfunction "1_1") (pintype "passive"))
      (node (ref "C44") (pin "1") (pinfunction "1_1") (pintype "passive"))
      (node (ref "C45") (pin "1") (pinfunction "1_1") (pintype "passive"))
      (node (ref "C46") (pin "1") (pinfunction "1_1") (pintype "passive"))
      (node (ref "C49") (pin "1") (pinfunction "1_1") (pintype "passive"))
      (node (ref "C50") (pin "1") (pinfunction "1_1") (pintype "passive"))
      (node (ref "C51") (pin "1") (pinfunction "1_1") (pintype "passive"))
      (node (ref "C53") (pin "1") (pinfunction "1_1") (pintype "passive"))
      (node (ref "C54") (pin "1") (pinfunction "1_1") (pintype "passive"))
      (node (ref "C55") (pin "1") (pinfunction "1_1") (pintype "passive"))
      (node (ref "INPUT_1") (pin "4") (pinfunction "4_4") (pintype "passive"))
      (node (ref "INPUT_2") (pin "4") (pinfunction "4_4") (pintype "passive"))
      (node (ref "INPUT_3") (pin "4") (pinfunction "4_4") (pintype "passive"))
      (node (ref "OUTPUT1") (pin "3") (pinfunction "3_3") (pintype "passive"))
      (node (ref "OUTPUT2") (pin "3") (pinfunction "3_3") (pintype "passive"))
      (node (ref "R18") (pin "1") (pinfunction "1_1") (pintype "passive"))
      (node (ref "U1") (pin "4") (pinfunction "GND1_4") (pintype "passive"))
      (node (ref "U14") (pin "2") (pinfunction "GND_2") (pintype "passive"))
      (node (ref "U15") (pin "4") (pinfunction "GND1_4") (pintype "passive"))
      (node (ref "U16") (pin "4") (pinfunction "GND1_4") (pintype "passive"))
      (node (ref "U17") (pin "5") (pinfunction "GND2_5") (pintype "passive"))
      (node (ref "U18") (pin "5") (pinfunction "GND2_5") (pintype "passive"))
      (node (ref "U19") (pin "2") (pinfunction "GND_2") (pintype "passive"))
      (node (ref "U20") (pin "3") (pinfunction "0V_3") (pintype "passive"))
    )
    (net (code "68") (name "Net-(D2-K)") (class "Default")
      (node (ref "C3") (pin "2") (pinfunction "2_2") (pintype "passive"))
      (node (ref "D2") (pin "2") (pinfunction "K_2") (pintype "passive"))
      (node (ref "L1") (pin "1") (pinfunction "1_1") (pintype "passive"))
      (node (ref "U2") (pin "8") (pinfunction "PH_8") (pintype "passive"))
    )
    (net (code "69") (name "Net-(D3-A)") (class "Default")
      (node (ref "D3") (pin "2") (pinfunction "A_2") (pintype "passive"))
      (node (ref "Q1") (pin "1") (pinfunction "G_1") (pintype "passive"))
      (node (ref "R4") (pin "2") (pinfunction "2_2") (pintype "passive"))
      (node (ref "R5") (pin "1") (pinfunction "1_1") (pintype "passive"))
    )
    (net (code "70") (name "Net-(D4-A)") (class "Default")
      (node (ref "D4") (pin "2") (pinfunction "A_2") (pintype "passive"))
      (node (ref "Q2") (pin "1") (pinfunction "G_1") (pintype "passive"))
      (node (ref "R6") (pin "1") (pinfunction "1_1") (pintype "passive"))
      (node (ref "R7") (pin "2") (pinfunction "2_2") (pintype "passive"))
    )
    (net (code "71") (name "Net-(D5-A)") (class "Default")
      (node (ref "D5") (pin "2") (pinfunction "A_2") (pintype "passive"))
      (node (ref "Q5") (pin "1") (pinfunction "G_1") (pintype "passive"))
      (node (ref "R16") (pin "2") (pinfunction "2_2") (pintype "passive"))
      (node (ref "R17") (pin "1") (pinfunction "1_1") (pintype "passive"))
    )
    (net (code "72") (name "Net-(D7-K)") (class "Default")
      (node (ref "D7") (pin "2") (pinfunction "K_2") (pintype "passive"))
      (node (ref "PWROUT1") (pin "1") (pinfunction "1_1") (pintype "passive"))
      (node (ref "Q1") (pin "2") (pinfunction "D_2") (pintype "passive"))
    )
    (net (code "73") (name "Net-(D8-K)") (class "Default")
      (node (ref "D8") (pin "2") (pinfunction "K_2") (pintype "passive"))
      (node (ref "PWROUT2") (pin "1") (pinfunction "1_1") (pintype "passive"))
      (node (ref "Q2") (pin "2") (pinfunction "D_2") (pintype "passive"))
    )
    (net (code "74") (name "Net-(D9-A)") (class "Default")
      (node (ref "D9") (pin "1") (pinfunction "A_1") (pintype "passive"))
      (node (ref "FAN1") (pin "2") (pinfunction "2_2") (pintype "passive"))
      (node (ref "FAN2") (pin "2") (pinfunction "2_2") (pintype "passive"))
      (node (ref "JP29") (pin "2") (pinfunction "2_2") (pintype "passive"))
      (node (ref "Q7") (pin "3") (pinfunction "D_3") (pintype "passive"))
    )
    (net (code "75") (name "Net-(D9-K)") (class "Default")
      (node (ref "D9") (pin "2") (pinfunction "K_2") (pintype "passive"))
      (node (ref "FAN1") (pin "1") (pinfunction "1_1") (pintype "passive"))
      (node (ref "FAN2") (pin "1") (pinfunction "1_1") (pintype "passive"))
      (node (ref "JP27") (pin "1") (pinfunction "1_1") (pintype "passive"))
      (node (ref "JP28") (pin "1") (pinfunction "1_1") (pintype "passive"))
    )
    (net (code "76") (name "Net-(INPUT_1-Pad2)") (class "Default")
      (node (ref "INPUT_1") (pin "2") (pinfunction "2_2") (pintype "passive"))
      (node (ref "R31") (pin "2") (pinfunction "2_2") (pintype "passive"))
    )
    (net (code "77") (name "Net-(INPUT_1-Pad3)") (class "Default")
      (node (ref "INPUT_1") (pin "3") (pinfunction "3_3") (pintype "passive"))
      (node (ref "R32") (pin "2") (pinfunction "2_2") (pintype "passive"))
    )
    (net (code "78") (name "Net-(INPUT_2-Pad2)") (class "Default")
      (node (ref "INPUT_2") (pin "2") (pinfunction "2_2") (pintype "passive"))
      (node (ref "R63") (pin "2") (pinfunction "2_2") (pintype "passive"))
    )
    (net (code "79") (name "Net-(INPUT_2-Pad3)") (class "Default")
      (node (ref "INPUT_2") (pin "3") (pinfunction "3_3") (pintype "passive"))
      (node (ref "R62") (pin "2") (pinfunction "2_2") (pintype "passive"))
    )
    (net (code "80") (name "Net-(INPUT_3-Pad2)") (class "Default")
      (node (ref "INPUT_3") (pin "2") (pinfunction "2_2") (pintype "passive"))
      (node (ref "R65") (pin "2") (pinfunction "2_2") (pintype "passive"))
    )
    (net (code "81") (name "Net-(INPUT_3-Pad3)") (class "Default")
      (node (ref "INPUT_3") (pin "3") (pinfunction "3_3") (pintype "passive"))
      (node (ref "R64") (pin "2") (pinfunction "2_2") (pintype "passive"))
    )
    (net (code "82") (name "Net-(LED1-A)") (class "Default")
      (node (ref "LED1") (pin "2") (pinfunction "A_2") (pintype "passive"))
      (node (ref "R3") (pin "1") (pinfunction "1_1") (pintype "passive"))
    )
    (net (code "83") (name "Net-(Q3-D)") (class "Default")
      (node (ref "Q3") (pin "3") (pinfunction "D_3") (pintype "passive"))
      (node (ref "R5") (pin "2") (pinfunction "2_2") (pintype "passive"))
    )
    (net (code "84") (name "Net-(Q4-D)") (class "Default")
      (node (ref "Q4") (pin "3") (pinfunction "D_3") (pintype "passive"))
      (node (ref "R6") (pin "2") (pinfunction "2_2") (pintype "passive"))
    )
    (net (code "85") (name "Net-(Q6-D)") (class "Default")
      (node (ref "Q6") (pin "3") (pinfunction "D_3") (pintype "passive"))
      (node (ref "R17") (pin "2") (pinfunction "2_2") (pintype "passive"))
    )
    (net (code "86") (name "Net-(Q9-B)") (class "Default")
      (node (ref "Q9") (pin "1") (pinfunction "B_1") (pintype "passive"))
      (node (ref "R19") (pin "1") (pinfunction "1_1") (pintype "passive"))
    )
    (net (code "87") (name "Net-(Q10-B)") (class "Default")
      (node (ref "Q10") (pin "1") (pinfunction "B_1") (pintype "passive"))
      (node (ref "R20") (pin "2") (pinfunction "2_2") (pintype "passive"))
    )
    (net (code "88") (name "Net-(R11-Pad3)") (class "Default")
      (node (ref "R11") (pin "3") (pinfunction "3_3") (pintype "passive"))
      (node (ref "R13") (pin "2") (pinfunction "2_2") (pintype "passive"))
    )
    (net (code "89") (name "Net-(R56-Pad2)") (class "Default")
      (node (ref "R56") (pin "2") (pinfunction "2_2") (pintype "passive"))
      (node (ref "RC1") (pin "3") (pinfunction "3_3") (pintype "passive"))
    )
    (net (code "90") (name "Net-(R59-Pad2)") (class "Default")
      (node (ref "R59") (pin "2") (pinfunction "2_2") (pintype "passive"))
      (node (ref "RC4") (pin "3") (pinfunction "3_3") (pintype "passive"))
    )
    (net (code "91") (name "Net-(U1-VIA)") (class "Default")
      (node (ref "C45") (pin "2") (pinfunction "2_2") (pintype "passive"))
      (node (ref "R31") (pin "1") (pinfunction "1_1") (pintype "passive"))
      (node (ref "U1") (pin "2") (pinfunction "VIA_2") (pintype "passive"))
    )
    (net (code "92") (name "Net-(U1-VIB)") (class "Default")
      (node (ref "C46") (pin "2") (pinfunction "2_2") (pintype "passive"))
      (node (ref "R32") (pin "1") (pinfunction "1_1") (pintype "passive"))
      (node (ref "U1") (pin "3") (pinfunction "VIB_3") (pintype "passive"))
    )
    (net (code "93") (name "Net-(U2-BOOT)") (class "Default")
      (node (ref "C3") (pin "1") (pinfunction "1_1") (pintype "passive"))
      (node (ref "U2") (pin "1") (pinfunction "BOOT_1") (pintype "passive"))
    )
    (net (code "94") (name "Net-(U2-VSENSE)") (class "Default")
      (node (ref "R1") (pin "1") (pinfunction "1_1") (pintype "passive"))
      (node (ref "R2") (pin "2") (pinfunction "2_2") (pintype "passive"))
      (node (ref "U2") (pin "4") (pinfunction "VSENSE_4") (pintype "passive"))
    )
    (net (code "95") (name "Net-(U3-Q7S)") (class "Default")
      (node (ref "U3") (pin "9") (pinfunction "Q7S_9") (pintype "passive"))
      (node (ref "U4") (pin "14") (pinfunction "DS_14") (pintype "passive"))
    )
    (net (code "96") (name "Net-(U4-Q7S)") (class "Default")
      (node (ref "U4") (pin "9") (pinfunction "Q7S_9") (pintype "passive"))
      (node (ref "U5") (pin "14") (pinfunction "DS_14") (pintype "passive"))
    )
    (net (code "97") (name "Net-(U6-1IN+)") (class "Default")
      (node (ref "C14") (pin "2") (pinfunction "2_2") (pintype "passive"))
      (node (ref "R10") (pin "2") (pinfunction "2_2") (pintype "passive"))
      (node (ref "U6") (pin "3") (pinfunction "1IN+_3") (pintype "passive"))
    )
    (net (code "98") (name "Net-(U6-1IN-)") (class "Default")
      (node (ref "R12") (pin "2") (pinfunction "2_2") (pintype "passive"))
      (node (ref "R13") (pin "1") (pinfunction "1_1") (pintype "passive"))
      (node (ref "U6") (pin "2") (pinfunction "1IN-_2") (pintype "passive"))
    )
    (net (code "99") (name "Net-(U7-AN)") (class "Default")
      (node (ref "R14") (pin "2") (pinfunction "2_2") (pintype "passive"))
      (node (ref "U7") (pin "1") (pinfunction "AN_1") (pintype "passive"))
    )
    (net (code "100") (name "Net-(U8-AN)") (class "Default")
      (node (ref "R15") (pin "2") (pinfunction "2_2") (pintype "passive"))
      (node (ref "U8") (pin "1") (pinfunction "AN_1") (pintype "passive"))
    )
    (net (code "101") (name "Net-(U9-DIAG1)") (class "Default")
      (node (ref "R53") (pin "1") (pinfunction "1_1") (pintype "passive"))
      (node (ref "U9") (pin "18") (pinfunction "DIAG1_18") (pintype "passive"))
    )
    (net (code "102") (name "Net-(U9-M1A)") (class "Default")
      (node (ref "JP21") (pin "1") (pinfunction "1_1") (pintype "passive"))
      (node (ref "U9") (pin "13") (pinfunction "M1A_13") (pintype "passive"))
      (node (ref "Y_MOTOR") (pin "3") (pinfunction "3_3") (pintype "passive"))
    )
    (net (code "103") (name "Net-(U9-M1B)") (class "Default")
      (node (ref "JP22") (pin "2") (pinfunction "2_2") (pintype "passive"))
      (node (ref "U9") (pin "14") (pinfunction "M1B_14") (pintype "passive"))
      (node (ref "Y_MOTOR") (pin "4") (pinfunction "4_4") (pintype "passive"))
    )
    (net (code "104") (name "Net-(U9-M2A)") (class "Default")
      (node (ref "JP20") (pin "1") (pinfunction "1_1") (pintype "passive"))
      (node (ref "U9") (pin "12") (pinfunction "M2A_12") (pintype "passive"))
      (node (ref "Y_MOTOR") (pin "2") (pinfunction "2_2") (pintype "passive"))
    )
    (net (code "105") (name "Net-(U9-M2B)") (class "Default")
      (node (ref "JP19") (pin "1") (pinfunction "1_1") (pintype "passive"))
      (node (ref "U9") (pin "11") (pinfunction "M2B_11") (pintype "passive"))
      (node (ref "Y_MOTOR") (pin "1") (pinfunction "1_1") (pintype "passive"))
    )
    (net (code "106") (name "Net-(U10-DIAG1)") (class "Default")
      (node (ref "R54") (pin "1") (pinfunction "1_1") (pintype "passive"))
      (node (ref "U10") (pin "18") (pinfunction "DIAG1_18") (pintype "passive"))
    )
    (net (code "107") (name "Net-(U10-M1A)") (class "Default")
      (node (ref "A_MOTOR") (pin "3") (pinfunction "3_3") (pintype "passive"))
      (node (ref "JP25") (pin "1") (pinfunction "1_1") (pintype "passive"))
      (node (ref "U10") (pin "13") (pinfunction "M1A_13") (pintype "passive"))
    )
    (net (code "108") (name "Net-(U10-M1B)") (class "Default")
      (node (ref "A_MOTOR") (pin "4") (pinfunction "4_4") (pintype "passive"))
      (node (ref "JP26") (pin "2") (pinfunction "2_2") (pintype "passive"))
      (node (ref "U10") (pin "14") (pinfunction "M1B_14") (pintype "passive"))
    )
    (net (code "109") (name "Net-(U10-M2A)") (class "Default")
      (node (ref "A_MOTOR") (pin "2") (pinfunction "2_2") (pintype "passive"))
      (node (ref "JP24") (pin "1") (pinfunction "1_1") (pintype "passive"))
      (node (ref "U10") (pin "12") (pinfunction "M2A_12") (pintype "passive"))
    )
    (net (code "110") (name "Net-(U10-M2B)") (class "Default")
      (node (ref "A_MOTOR") (pin "1") (pinfunction "1_1") (pintype "passive"))
      (node (ref "JP23") (pin "1") (pinfunction "1_1") (pintype "passive"))
      (node (ref "U10") (pin "11") (pinfunction "M2B_11") (pintype "passive"))
    )
    (net (code "111") (name "Net-(U11-DIAG1)") (class "Default")
      (node (ref "R61") (pin "1") (pinfunction "1_1") (pintype "passive"))
      (node (ref "U11") (pin "18") (pinfunction "DIAG1_18") (pintype "passive"))
    )
    (net (code "112") (name "Net-(U11-M1A)") (class "Default")
      (node (ref "JP3") (pin "1") (pinfunction "1_1") (pintype "passive"))
      (node (ref "U11") (pin "13") (pinfunction "M1A_13") (pintype "passive"))
      (node (ref "X_MOTOR") (pin "3") (pinfunction "3_3") (pintype "passive"))
    )
    (net (code "113") (name "Net-(U11-M1B)") (class "Default")
      (node (ref "JP1") (pin "2") (pinfunction "2_2") (pintype "passive"))
      (node (ref "U11") (pin "14") (pinfunction "M1B_14") (pintype "passive"))
      (node (ref "X_MOTOR") (pin "4") (pinfunction "4_4") (pintype "passive"))
    )
    (net (code "114") (name "Net-(U11-M2A)") (class "Default")
      (node (ref "JP2") (pin "1") (pinfunction "1_1") (pintype "passive"))
      (node (ref "U11") (pin "12") (pinfunction "M2A_12") (pintype "passive"))
      (node (ref "X_MOTOR") (pin "2") (pinfunction "2_2") (pintype "passive"))
    )
    (net (code "115") (name "Net-(U11-M2B)") (class "Default")
      (node (ref "JP4") (pin "1") (pinfunction "1_1") (pintype "passive"))
      (node (ref "U11") (pin "11") (pinfunction "M2B_11") (pintype "passive"))
      (node (ref "X_MOTOR") (pin "1") (pinfunction "1_1") (pintype "passive"))
    )
    (net (code "116") (name "Net-(U12-DIAG1)") (class "Default")
      (node (ref "R52") (pin "1") (pinfunction "1_1") (pintype "passive"))
      (node (ref "U12") (pin "18") (pinfunction "DIAG1_18") (pintype "passive"))
    )
    (net (code "117") (name "Net-(U12-M1A)") (class "Default")
      (node (ref "JP17") (pin "1") (pinfunction "1_1") (pintype "passive"))
      (node (ref "U12") (pin "13") (pinfunction "M1A_13") (pintype "passive"))
      (node (ref "Z_MOTOR") (pin "3") (pinfunction "3_3") (pintype "passive"))
    )
    (net (code "118") (name "Net-(U12-M1B)") (class "Default")
      (node (ref "JP18") (pin "2") (pinfunction "2_2") (pintype "passive"))
      (node (ref "U12") (pin "14") (pinfunction "M1B_14") (pintype "passive"))
      (node (ref "Z_MOTOR") (pin "4") (pinfunction "4_4") (pintype "passive"))
    )
    (net (code "119") (name "Net-(U12-M2A)") (class "Default")
      (node (ref "JP16") (pin "1") (pinfunction "1_1") (pintype "passive"))
      (node (ref "U12") (pin "12") (pinfunction "M2A_12") (pintype "passive"))
      (node (ref "Z_MOTOR") (pin "2") (pinfunction "2_2") (pintype "passive"))
    )
    (net (code "120") (name "Net-(U12-M2B)") (class "Default")
      (node (ref "JP15") (pin "1") (pinfunction "1_1") (pintype "passive"))
      (node (ref "U12") (pin "11") (pinfunction "M2B_11") (pintype "passive"))
      (node (ref "Z_MOTOR") (pin "1") (pinfunction "1_1") (pintype "passive"))
    )
    (net (code "121") (name "Net-(U14-1A)") (class "Default")
      (node (ref "U14") (pin "1") (pinfunction "1A_1") (pintype "passive"))
      (node (ref "U17") (pin "7") (pinfunction "VOA_7") (pintype "passive"))
    )
    (net (code "122") (name "Net-(U14-1Y)") (class "Default")
      (node (ref "OUTPUT1") (pin "1") (pinfunction "1_1") (pintype "passive"))
      (node (ref "U14") (pin "6") (pinfunction "1Y_6") (pintype "passive"))
    )
    (net (code "123") (name "Net-(U14-2A)") (class "Default")
      (node (ref "U14") (pin "3") (pinfunction "2A_3") (pintype "passive"))
      (node (ref "U17") (pin "6") (pinfunction "VOB_6") (pintype "passive"))
    )
    (net (code "124") (name "Net-(U14-2Y)") (class "Default")
      (node (ref "OUTPUT1") (pin "2") (pinfunction "2_2") (pintype "passive"))
      (node (ref "U14") (pin "4") (pinfunction "2Y_4") (pintype "passive"))
    )
    (net (code "125") (name "Net-(U15-VIA)") (class "Default")
      (node (ref "C50") (pin "2") (pinfunction "2_2") (pintype "passive"))
      (node (ref "R63") (pin "1") (pinfunction "1_1") (pintype "passive"))
      (node (ref "U15") (pin "2") (pinfunction "VIA_2") (pintype "passive"))
    )
    (net (code "126") (name "Net-(U15-VIB)") (class "Default")
      (node (ref "C49") (pin "2") (pinfunction "2_2") (pintype "passive"))
      (node (ref "R62") (pin "1") (pinfunction "1_1") (pintype "passive"))
      (node (ref "U15") (pin "3") (pinfunction "VIB_3") (pintype "passive"))
    )
    (net (code "127") (name "Net-(U16-VIA)") (class "Default")
      (node (ref "C54") (pin "2") (pinfunction "2_2") (pintype "passive"))
      (node (ref "R65") (pin "1") (pinfunction "1_1") (pintype "passive"))
      (node (ref "U16") (pin "2") (pinfunction "VIA_2") (pintype "passive"))
    )
    (net (code "128") (name "Net-(U16-VIB)") (class "Default")
      (node (ref "C53") (pin "2") (pinfunction "2_2") (pintype "passive"))
      (node (ref "R64") (pin "1") (pinfunction "1_1") (pintype "passive"))
      (node (ref "U16") (pin "3") (pinfunction "VIB_3") (pintype "passive"))
    )
    (net (code "129") (name "Net-(U18-VOA)") (class "Default")
      (node (ref "U18") (pin "7") (pinfunction "VOA_7") (pintype "passive"))
      (node (ref "U19") (pin "1") (pinfunction "1A_1") (pintype "passive"))
    )
    (net (code "130") (name "Net-(U18-VOB)") (class "Default")
      (node (ref "U18") (pin "6") (pinfunction "VOB_6") (pintype "passive"))
      (node (ref "U19") (pin "3") (pinfunction "2A_3") (pintype "passive"))
    )
    (net (code "131") (name "Net-(U19-1Y)") (class "Default")
      (node (ref "OUTPUT2") (pin "1") (pinfunction "1_1") (pintype "passive"))
      (node (ref "U19") (pin "6") (pinfunction "1Y_6") (pintype "passive"))
    )
    (net (code "132") (name "Net-(U19-2Y)") (class "Default")
      (node (ref "OUTPUT2") (pin "2") (pinfunction "2_2") (pintype "passive"))
      (node (ref "U19") (pin "4") (pinfunction "2Y_4") (pintype "passive"))
    )
    (net (code "133") (name "Net-(U29-D+)") (class "Default")
      (node (ref "D12") (pin "2") (pinfunction "2_2") (pintype "passive"))
      (node (ref "U29") (pin "4") (pinfunction "D+_4") (pintype "passive"))
      (node (ref "USB1") (pin "3") (pinfunction "D+_3") (pintype "passive"))
    )
    (net (code "134") (name "Net-(U29-D-)") (class "Default")
      (node (ref "D11") (pin "2") (pinfunction "2_2") (pintype "passive"))
      (node (ref "U29") (pin "5") (pinfunction "D-_5") (pintype "passive"))
      (node (ref "USB1") (pin "2") (pinfunction "D-_2") (pintype "passive"))
    )
    (net (code "135") (name "Net-(U29-RST#)") (class "Default")
      (node (ref "R60") (pin "1") (pinfunction "1_1") (pintype "passive"))
      (node (ref "U29") (pin "9") (pinfunction "RST#_9") (pintype "passive"))
    )
    (net (code "136") (name "VBUS") (class "Default")
      (node (ref "C37") (pin "2") (pinfunction "2_2") (pintype "passive"))
      (node (ref "C38") (pin "2") (pinfunction "2_2") (pintype "passive"))
      (node (ref "C39") (pin "2") (pinfunction "2_2") (pintype "passive"))
      (node (ref "D1") (pin "2") (pinfunction "2_2") (pintype "passive"))
      (node (ref "D10") (pin "2") (pinfunction "K_2") (pintype "passive"))
      (node (ref "U28") (pin "3") (pinfunction "Vin_3") (pintype "passive"))
      (node (ref "U29") (pin "7") (pinfunction "REGIN_7") (pintype "passive"))
      (node (ref "U29") (pin "8") (pinfunction "VBUS_8") (pintype "passive"))
      (node (ref "USB1") (pin "1") (pinfunction "V+_1") (pintype "passive"))
    )
    (net (code "137") (name "VCC") (class "Default")
      (node (ref "C10") (pin "2") (pinfunction "2_2") (pintype "passive"))
      (node (ref "C11") (pin "2") (pinfunction "2_2") (pintype "passive"))
      (node (ref "C12") (pin "2") (pinfunction "2_2") (pintype "passive"))
      (node (ref "C15") (pin "2") (pinfunction "2_2") (pintype "passive"))
      (node (ref "C18") (pin "2") (pinfunction "2_2") (pintype "passive"))
      (node (ref "C19") (pin "2") (pinfunction "2_2") (pintype "passive"))
      (node (ref "C22") (pin "2") (pinfunction "2_2") (pintype "passive"))
      (node (ref "C25") (pin "2") (pinfunction "2_2") (pintype "passive"))
      (node (ref "C26") (pin "2") (pinfunction "2_2") (pintype "passive"))
      (node (ref "JP1") (pin "1") (pinfunction "1_1") (pintype "passive"))
      (node (ref "JP10") (pin "2") (pinfunction "2_2") (pintype "passive"))
      (node (ref "JP11") (pin "1") (pinfunction "1_1") (pintype "passive"))
      (node (ref "JP13") (pin "1") (pinfunction "1_1") (pintype "passive"))
      (node (ref "JP18") (pin "1") (pinfunction "1_1") (pintype "passive"))
      (node (ref "JP22") (pin "1") (pinfunction "1_1") (pintype "passive"))
      (node (ref "JP26") (pin "1") (pinfunction "1_1") (pintype "passive"))
      (node (ref "JP5") (pin "1") (pinfunction "1_1") (pintype "passive"))
      (node (ref "JP7") (pin "1") (pinfunction "1_1") (pintype "passive"))
      (node (ref "JP9") (pin "2") (pinfunction "2_2") (pintype "passive"))
      (node (ref "U10") (pin "15") (pinfunction "VIO_15") (pintype "passive"))
      (node (ref "U11") (pin "15") (pinfunction "VIO_15") (pintype "passive"))
      (node (ref "U12") (pin "15") (pinfunction "VIO_15") (pintype "passive"))
      (node (ref "U17") (pin "1") (pinfunction "VDD1_1") (pintype "passive"))
      (node (ref "U18") (pin "1") (pinfunction "VDD1_1") (pintype "passive"))
      (node (ref "U3") (pin "10") (pinfunction "MR#_10") (pintype "passive"))
      (node (ref "U3") (pin "16") (pinfunction "VCC_16") (pintype "passive"))
      (node (ref "U4") (pin "10") (pinfunction "MR#_10") (pintype "passive"))
      (node (ref "U4") (pin "16") (pinfunction "VCC_16") (pintype "passive"))
      (node (ref "U5") (pin "10") (pinfunction "MR#_10") (pintype "passive"))
      (node (ref "U5") (pin "16") (pinfunction "VCC_16") (pintype "passive"))
      (node (ref "U9") (pin "15") (pinfunction "VIO_15") (pintype "passive"))
    )
    (net (code "138") (name "VDD") (class "Default")
      (node (ref "C40") (pin "2") (pinfunction "2_2") (pintype "passive"))
      (node (ref "R60") (pin "2") (pinfunction "2_2") (pintype "passive"))
      (node (ref "U29") (pin "6") (pinfunction "VDD_6") (pintype "passive"))
    )
    (net (code "139") (name "VP") (class "Default")
      (node (ref "C13") (pin "2") (pinfunction "2_2") (pintype "passive"))
      (node (ref "C16") (pin "1") (pinfunction "1_1") (pintype "passive"))
      (node (ref "C17") (pin "1") (pinfunction "1_1") (pintype "passive"))
      (node (ref "C20") (pin "1") (pinfunction "1_1") (pintype "passive"))
      (node (ref "C21") (pin "1") (pinfunction "1_1") (pintype "passive"))
      (node (ref "C4") (pin "2") (pinfunction "2_2") (pintype "passive"))
      (node (ref "C5") (pin "2") (pinfunction "2_2") (pintype "passive"))
      (node (ref "C6") (pin "2") (pinfunction "2_2") (pintype "passive"))
      (node (ref "D3") (pin "1") (pinfunction "K_1") (pintype "passive"))
      (node (ref "D4") (pin "1") (pinfunction "K_1") (pintype "passive"))
      (node (ref "D5") (pin "1") (pinfunction "K_1") (pintype "passive"))
      (node (ref "JP27") (pin "2") (pinfunction "2_2") (pintype "passive"))
      (node (ref "PWR") (pin "1") (pinfunction "1_1") (pintype "passive"))
      (node (ref "Q1") (pin "3") (pinfunction "S_3") (pintype "passive"))
      (node (ref "Q2") (pin "3") (pinfunction "S_3") (pintype "passive"))
      (node (ref "Q5") (pin "3") (pinfunction "S_3") (pintype "passive"))
      (node (ref "R16") (pin "1") (pinfunction "1_1") (pintype "passive"))
      (node (ref "R4") (pin "1") (pinfunction "1_1") (pintype "passive"))
      (node (ref "R7") (pin "1") (pinfunction "1_1") (pintype "passive"))
      (node (ref "U10") (pin "9") (pinfunction "VM_9") (pintype "passive"))
      (node (ref "U11") (pin "9") (pinfunction "VM_9") (pintype "passive"))
      (node (ref "U12") (pin "9") (pinfunction "VM_9") (pintype "passive"))
      (node (ref "U2") (pin "7") (pinfunction "VIN_7") (pintype "passive"))
      (node (ref "U6") (pin "8") (pinfunction "VCC_8") (pintype "passive"))
      (node (ref "U9") (pin "9") (pinfunction "VM_9") (pintype "passive"))
    )
    (net (code "140") (name "unconnected-(ESC-Pad2)") (class "Default")
      (node (ref "ESC") (pin "2") (pinfunction "2_2") (pintype "passive+no_connect"))
    )
    (net (code "141") (name "unconnected-(H1-Pad1)") (class "Default")
      (node (ref "H1") (pin "1") (pinfunction "1_1") (pintype "passive+no_connect"))
    )
    (net (code "142") (name "unconnected-(H2-Pad1)") (class "Default")
      (node (ref "H2") (pin "1") (pinfunction "1_1") (pintype "passive+no_connect"))
    )
    (net (code "143") (name "unconnected-(H3-Pad1)") (class "Default")
      (node (ref "H3") (pin "1") (pinfunction "1_1") (pintype "passive+no_connect"))
    )
    (net (code "144") (name "unconnected-(H4-Pad1)") (class "Default")
      (node (ref "H4") (pin "1") (pinfunction "1_1") (pintype "passive+no_connect"))
    )
    (net (code "145") (name "unconnected-(MICROSD-CD-Pad9)") (class "Default")
      (node (ref "MICROSD") (pin "9") (pinfunction "CD_9") (pintype "passive+no_connect"))
    )
    (net (code "146") (name "unconnected-(MICROSD-DAT1(RSV)-Pad8)") (class "Default")
      (node (ref "MICROSD") (pin "8") (pinfunction "DAT1(RSV)_8") (pintype "passive+no_connect"))
    )
    (net (code "147") (name "unconnected-(MICROSD-DAT2(RSV)-Pad1)") (class "Default")
      (node (ref "MICROSD") (pin "1") (pinfunction "DAT2(RSV)_1") (pintype "passive+no_connect"))
    )
    (net (code "148") (name "unconnected-(R11-Pad1)") (class "Default")
      (node (ref "R11") (pin "1") (pinfunction "1_1") (pintype "passive+no_connect"))
    )
    (net (code "149") (name "unconnected-(U2-ENA-Pad5)") (class "Default")
      (node (ref "U2") (pin "5") (pinfunction "ENA_5") (pintype "passive+no_connect"))
    )
    (net (code "150") (name "unconnected-(U2-NC-Pad2)") (class "Default")
      (node (ref "U2") (pin "2") (pinfunction "NC_2") (pintype "passive+no_connect"))
    )
    (net (code "151") (name "unconnected-(U2-NC-Pad3)") (class "Default")
      (node (ref "U2") (pin "3") (pinfunction "NC_3") (pintype "passive+no_connect"))
    )
    (net (code "152") (name "unconnected-(U5-Q7S-Pad9)") (class "Default")
      (node (ref "U5") (pin "9") (pinfunction "Q7S_9") (pintype "passive+no_connect"))
    )
    (net (code "153") (name "unconnected-(U6-2IN+-Pad5)") (class "Default")
      (node (ref "U6") (pin "5") (pinfunction "2IN+_5") (pintype "passive+no_connect"))
    )
    (net (code "154") (name "unconnected-(U6-2IN--Pad6)") (class "Default")
      (node (ref "U6") (pin "6") (pinfunction "2IN-_6") (pintype "passive+no_connect"))
    )
    (net (code "155") (name "unconnected-(U6-2OUT-Pad7)") (class "Default")
      (node (ref "U6") (pin "7") (pinfunction "2OUT_7") (pintype "passive+no_connect"))
    )
    (net (code "156") (name "unconnected-(U9-DIAG0-Pad17)") (class "Default")
      (node (ref "U9") (pin "17") (pinfunction "DIAG0_17") (pintype "passive+no_connect"))
    )
    (net (code "157") (name "unconnected-(U10-DIAG0-Pad17)") (class "Default")
      (node (ref "U10") (pin "17") (pinfunction "DIAG0_17") (pintype "passive+no_connect"))
    )
    (net (code "158") (name "unconnected-(U11-DIAG0-Pad17)") (class "Default")
      (node (ref "U11") (pin "17") (pinfunction "DIAG0_17") (pintype "passive+no_connect"))
    )
    (net (code "159") (name "unconnected-(U12-DIAG0-Pad17)") (class "Default")
      (node (ref "U12") (pin "17") (pinfunction "DIAG0_17") (pintype "passive+no_connect"))
    )
    (net (code "160") (name "unconnected-(U26-CLK-Pad20)") (class "Default")
      (node (ref "U26") (pin "20") (pinfunction "CLK_20") (pintype "passive+no_connect"))
    )
    (net (code "161") (name "unconnected-(U26-CMD-Pad19)") (class "Default")
      (node (ref "U26") (pin "19") (pinfunction "CMD_19") (pintype "passive+no_connect"))
    )
    (net (code "162") (name "unconnected-(U26-NC-Pad32)") (class "Default")
      (node (ref "U26") (pin "32") (pinfunction "NC_32") (pintype "passive+no_connect"))
    )
    (net (code "163") (name "unconnected-(U26-SD0-Pad21)") (class "Default")
      (node (ref "U26") (pin "21") (pinfunction "SD0_21") (pintype "passive+no_connect"))
    )
    (net (code "164") (name "unconnected-(U26-SD1-Pad22)") (class "Default")
      (node (ref "U26") (pin "22") (pinfunction "SD1_22") (pintype "passive+no_connect"))
    )
    (net (code "165") (name "unconnected-(U26-SD2-Pad17)") (class "Default")
      (node (ref "U26") (pin "17") (pinfunction "SD2_17") (pintype "passive+no_connect"))
    )
    (net (code "166") (name "unconnected-(U26-SD3-Pad18)") (class "Default")
      (node (ref "U26") (pin "18") (pinfunction "SD3_18") (pintype "passive+no_connect"))
    )
    (net (code "167") (name "unconnected-(U29-CTS-Pad23)") (class "Default")
      (node (ref "U29") (pin "23") (pinfunction "CTS_23") (pintype "passive+no_connect"))
    )
    (net (code "168") (name "unconnected-(U29-DCD-Pad1)") (class "Default")
      (node (ref "U29") (pin "1") (pinfunction "DCD_1") (pintype "passive+no_connect"))
    )
    (net (code "169") (name "unconnected-(U29-DSR-Pad27)") (class "Default")
      (node (ref "U29") (pin "27") (pinfunction "DSR_27") (pintype "passive+no_connect"))
    )
    (net (code "170") (name "unconnected-(U29-EP-Pad29)") (class "Default")
      (node (ref "U29") (pin "29") (pinfunction "EP_29") (pintype "passive+no_connect"))
    )
    (net (code "171") (name "unconnected-(U29-NC-Pad10)") (class "Default")
      (node (ref "U29") (pin "10") (pinfunction "NC_10") (pintype "passive+no_connect"))
    )
    (net (code "172") (name "unconnected-(U29-NC-Pad13)") (class "Default")
      (node (ref "U29") (pin "13") (pinfunction "NC_13") (pintype "passive+no_connect"))
    )
    (net (code "173") (name "unconnected-(U29-NC-Pad14)") (class "Default")
      (node (ref "U29") (pin "14") (pinfunction "NC_14") (pintype "passive+no_connect"))
    )
    (net (code "174") (name "unconnected-(U29-NC-Pad15)") (class "Default")
      (node (ref "U29") (pin "15") (pinfunction "NC_15") (pintype "passive+no_connect"))
    )
    (net (code "175") (name "unconnected-(U29-NC-Pad16)") (class "Default")
      (node (ref "U29") (pin "16") (pinfunction "NC_16") (pintype "passive+no_connect"))
    )
    (net (code "176") (name "unconnected-(U29-NC-Pad17)") (class "Default")
      (node (ref "U29") (pin "17") (pinfunction "NC_17") (pintype "passive+no_connect"))
    )
    (net (code "177") (name "unconnected-(U29-NC-Pad18)") (class "Default")
      (node (ref "U29") (pin "18") (pinfunction "NC_18") (pintype "passive+no_connect"))
    )
    (net (code "178") (name "unconnected-(U29-NC-Pad19)") (class "Default")
      (node (ref "U29") (pin "19") (pinfunction "NC_19") (pintype "passive+no_connect"))
    )
    (net (code "179") (name "unconnected-(U29-NC-Pad20)") (class "Default")
      (node (ref "U29") (pin "20") (pinfunction "NC_20") (pintype "passive+no_connect"))
    )
    (net (code "180") (name "unconnected-(U29-NC-Pad21)") (class "Default")
      (node (ref "U29") (pin "21") (pinfunction "NC_21") (pintype "passive+no_connect"))
    )
    (net (code "181") (name "unconnected-(U29-NC-Pad22)") (class "Default")
      (node (ref "U29") (pin "22") (pinfunction "NC_22") (pintype "passive+no_connect"))
    )
    (net (code "182") (name "unconnected-(U29-RI-Pad2)") (class "Default")
      (node (ref "U29") (pin "2") (pinfunction "RI_2") (pintype "passive+no_connect"))
    )
    (net (code "183") (name "unconnected-(U29-SUSPEND#-Pad11)") (class "Default")
      (node (ref "U29") (pin "11") (pinfunction "SUSPEND#_11") (pintype "passive+no_connect"))
    )
    (net (code "184") (name "unconnected-(U29-SUSPEND-Pad12)") (class "Default")
      (node (ref "U29") (pin "12") (pinfunction "SUSPEND_12") (pintype "passive+no_connect"))
    )
    (net (code "185") (name "unconnected-(USB1-ID-Pad4)") (class "Default")
      (node (ref "USB1") (pin "4") (pinfunction "ID_4") (pintype "passive+no_connect"))
    )
  )
)
